# Rev_1.net
KiCad netlist of a schematic drawn in EAGLE
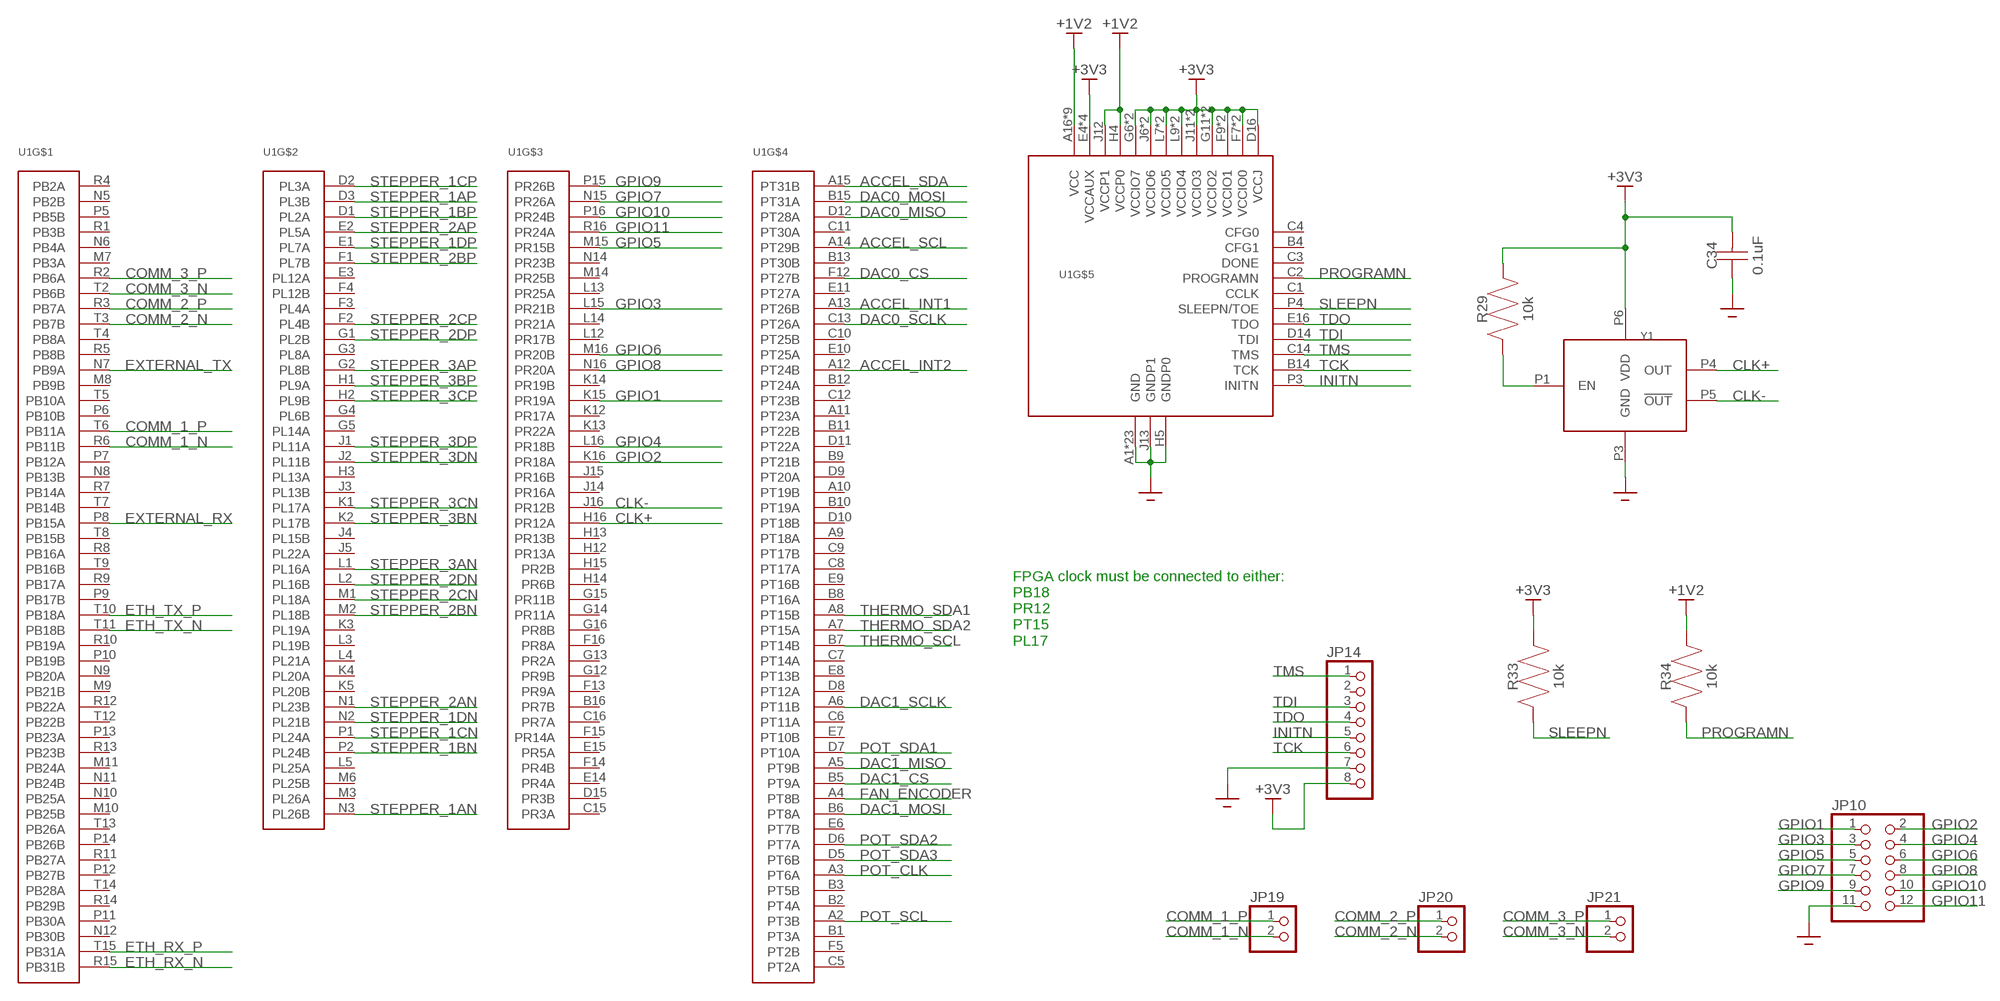
[diagram p0: schematic, sheet 1]
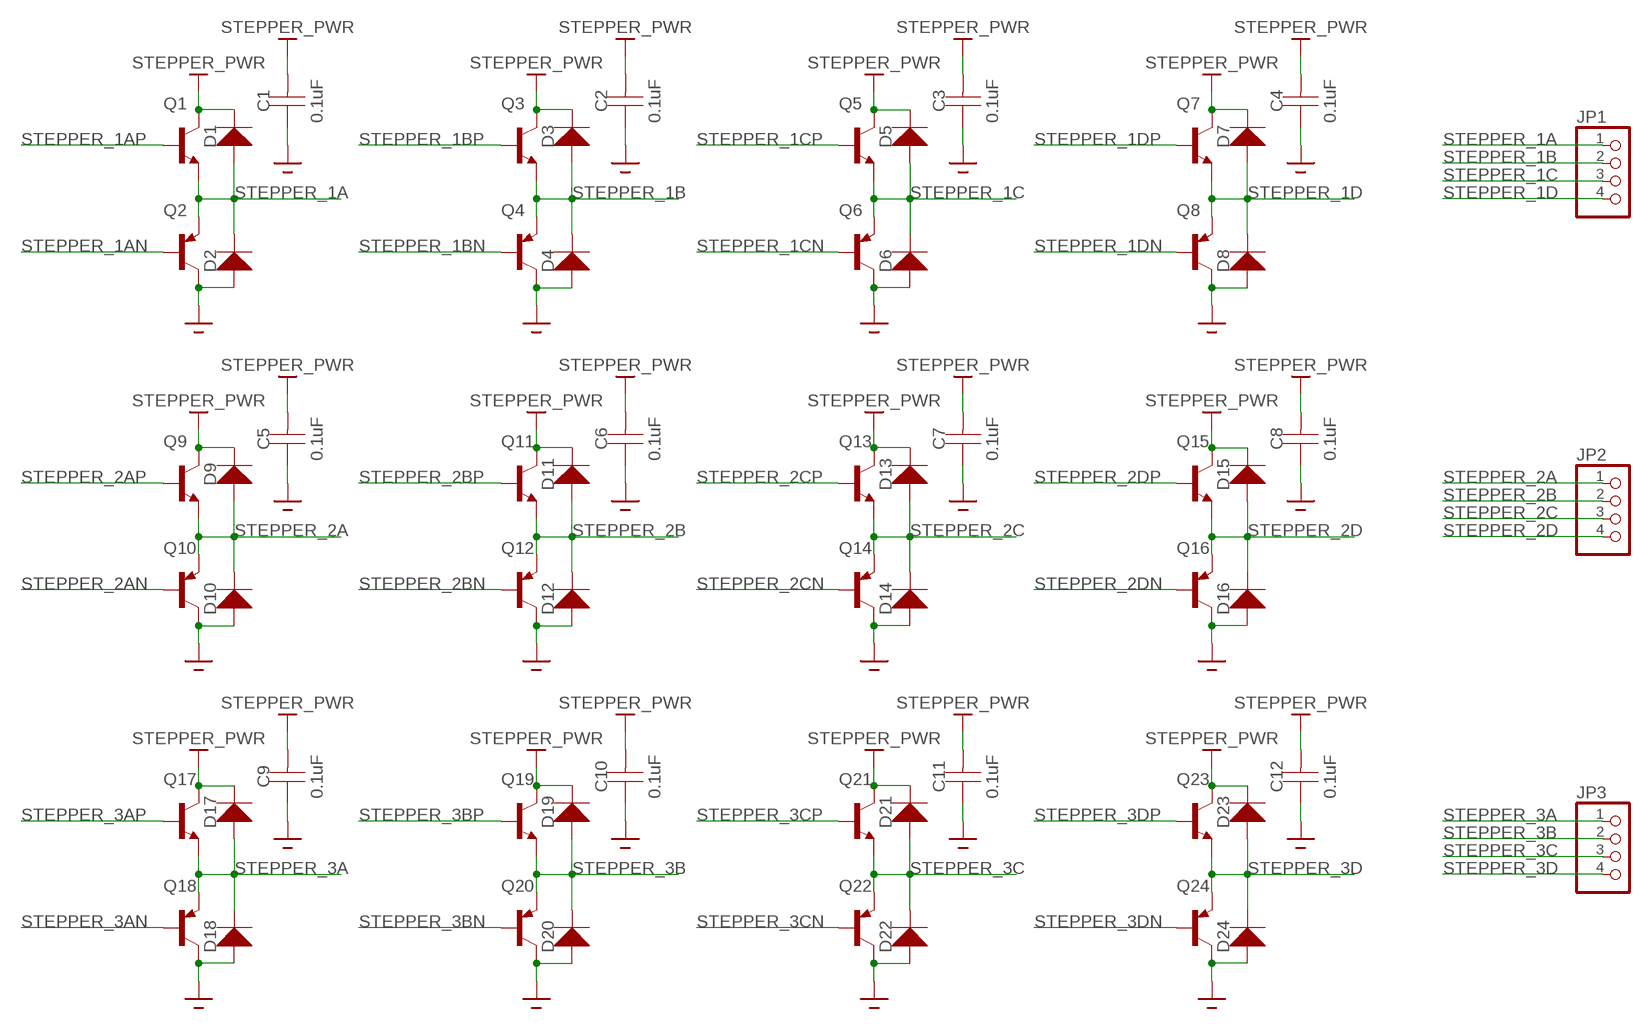
[diagram p1: schematic, sheet 2]
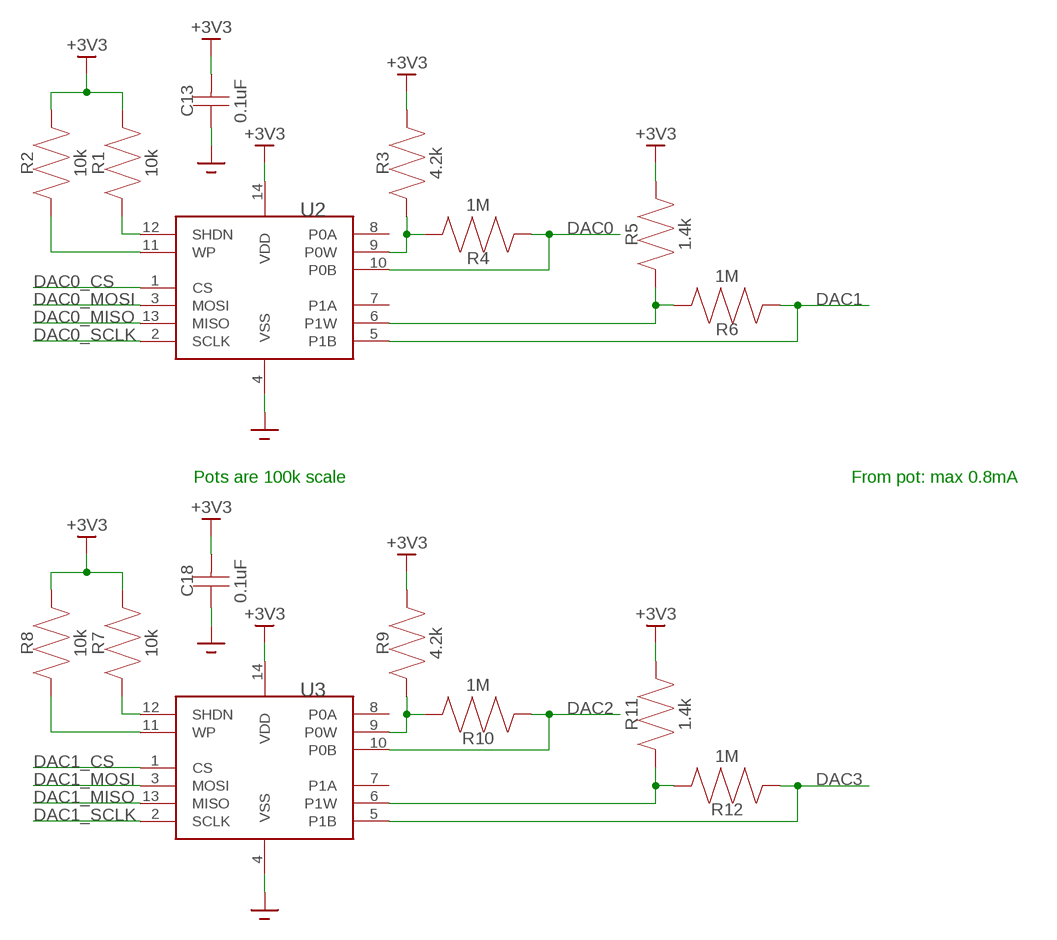
[diagram p2: schematic, sheet 3]
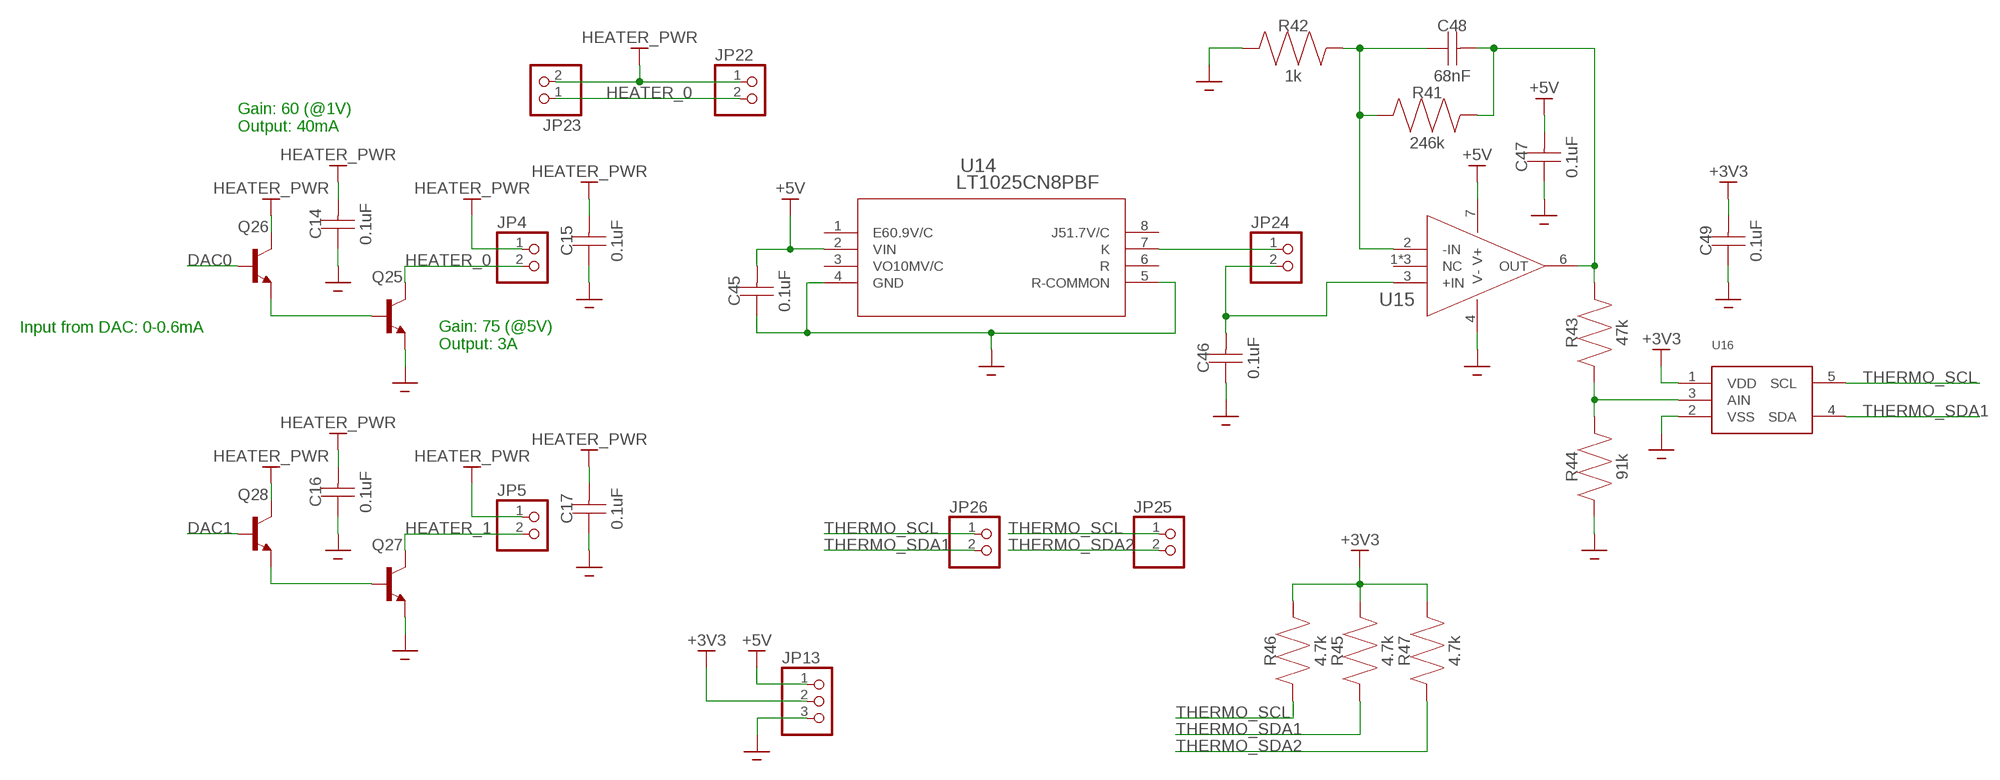
[diagram p3: schematic, sheet 4]
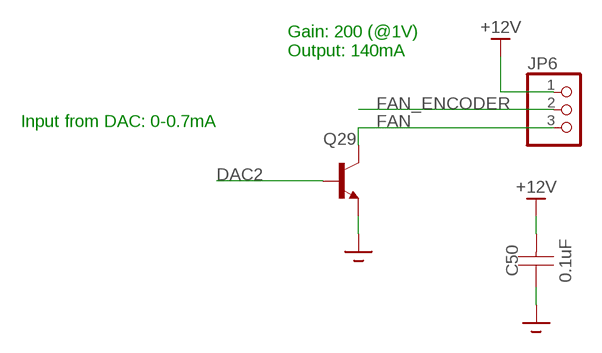
[diagram p4: schematic, sheet 5]
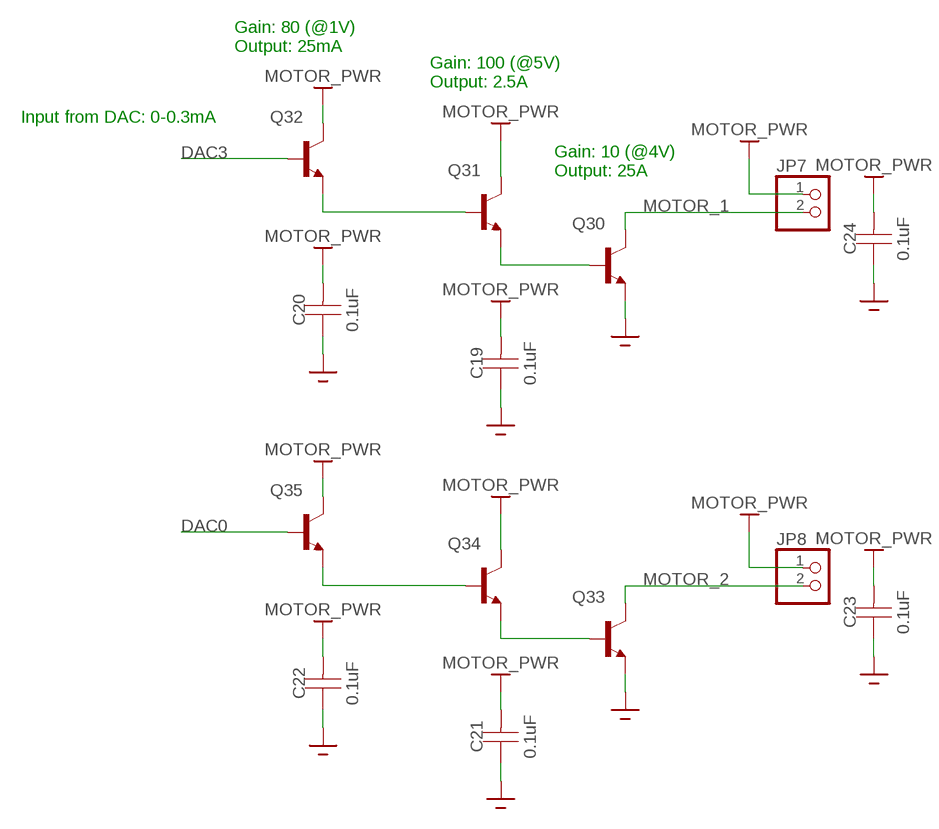
[diagram p5: schematic, sheet 6]
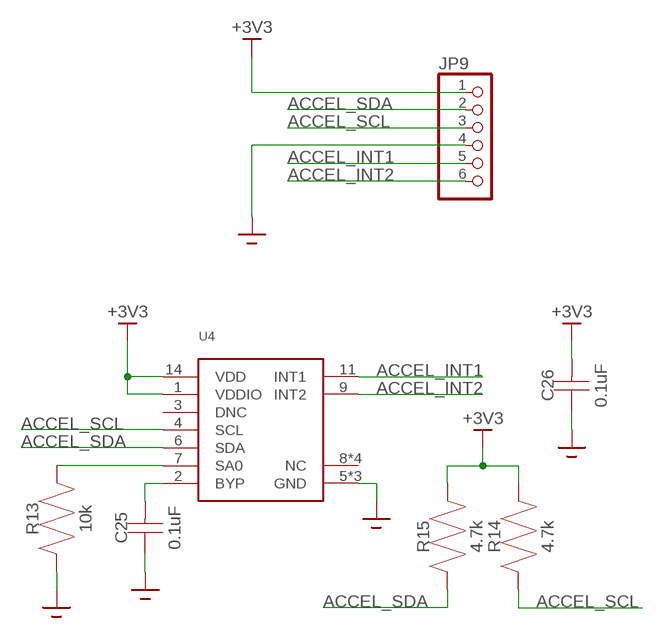
[diagram p6: schematic, sheet 7]
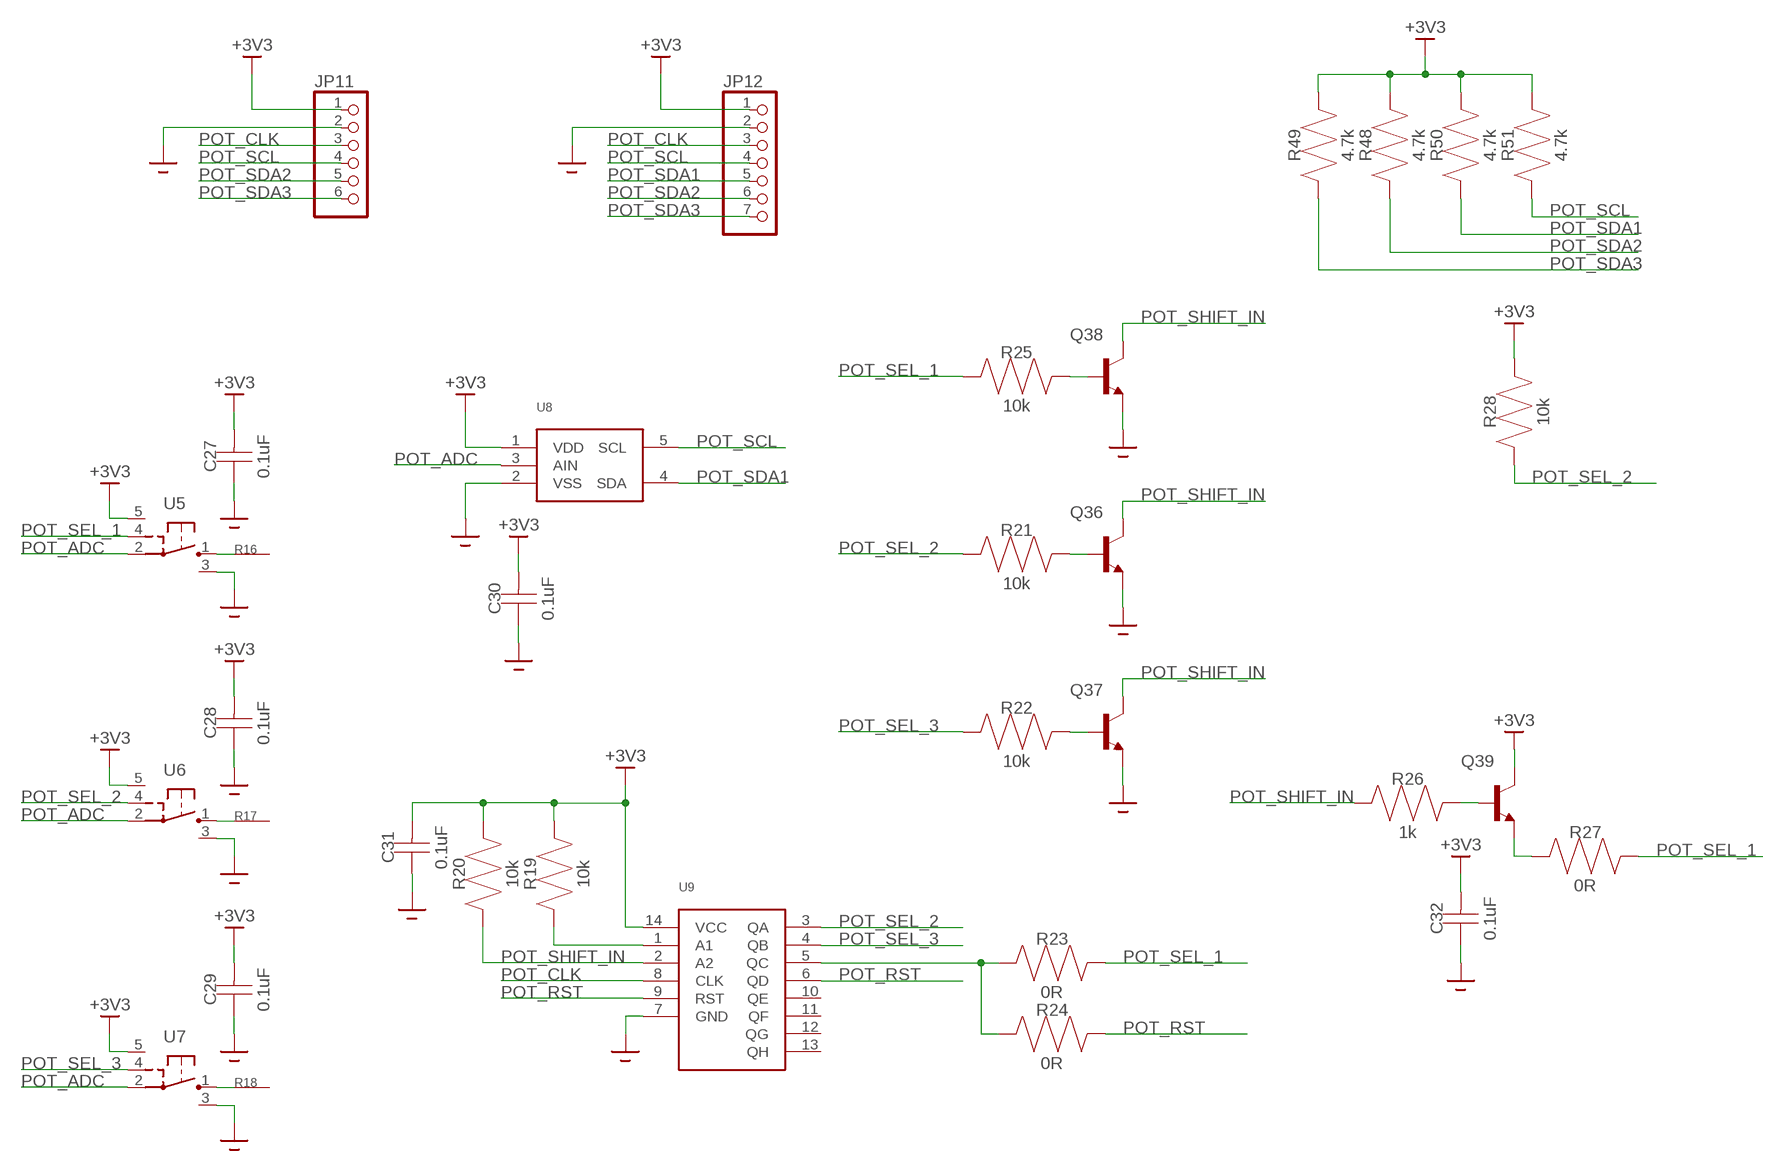
[diagram p7: schematic, sheet 8]
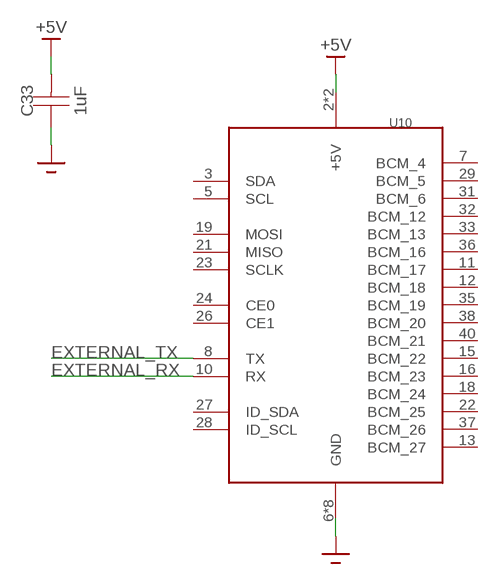
[diagram p8: schematic, sheet 9]
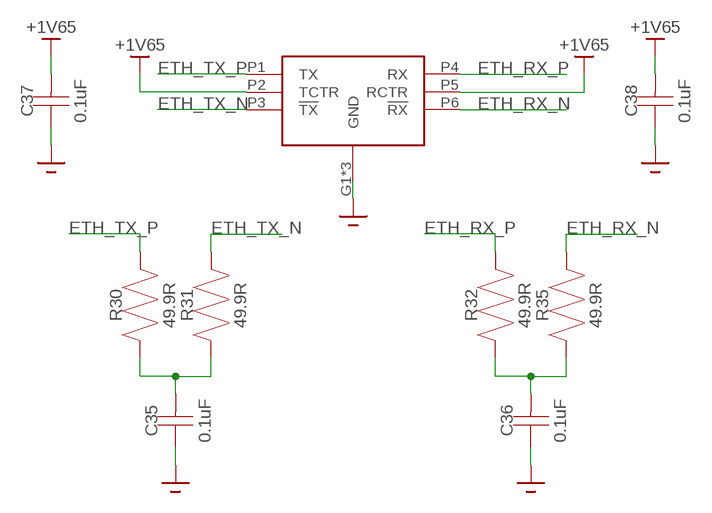
[diagram p9: schematic, sheet 10]
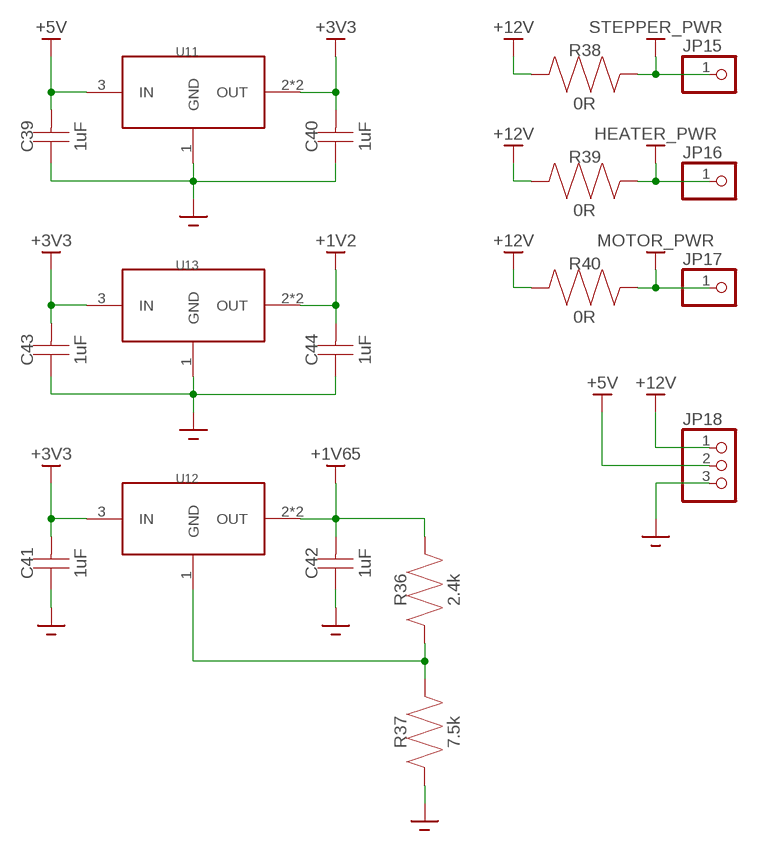
[diagram p10: schematic, sheet 11]
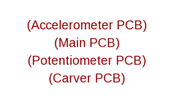
[diagram p11: schematic, sheet 12]

(export (version "E")
  (design (tool "Eeschema 10.0.6"))
  (components
    (comp (ref "C35")
      (value "0.1uF")
      (footprint "eagle-import:0805")
      (libsource (lib "eagle-import") (part "CAPACITOR0805"))
    )
    (comp (ref "C36")
      (value "0.1uF")
      (footprint "eagle-import:0805")
      (libsource (lib "eagle-import") (part "CAPACITOR0805"))
    )
    (comp (ref "C37")
      (value "0.1uF")
      (footprint "eagle-import:0805")
      (libsource (lib "eagle-import") (part "CAPACITOR0805"))
    )
    (comp (ref "C38")
      (value "0.1uF")
      (footprint "eagle-import:0805")
      (libsource (lib "eagle-import") (part "CAPACITOR0805"))
    )
    (comp (ref "P1")
      (value "5-2301994-4")
      (footprint "eagle-import:5-2301994-4")
      (libsource (lib "eagle-import") (part "5-2301994-4"))
    )
    (comp (ref "R30")
      (value "49.9R")
      (footprint "eagle-import:0805")
      (libsource (lib "eagle-import") (part "RESISTOR0805"))
    )
    (comp (ref "R31")
      (value "49.9R")
      (footprint "eagle-import:0805")
      (libsource (lib "eagle-import") (part "RESISTOR0805"))
    )
    (comp (ref "R32")
      (value "49.9R")
      (footprint "eagle-import:0805")
      (libsource (lib "eagle-import") (part "RESISTOR0805"))
    )
    (comp (ref "R35")
      (value "49.9R")
      (footprint "eagle-import:0805")
      (libsource (lib "eagle-import") (part "RESISTOR0805"))
    )
    (comp (ref "C19")
      (value "0.1uF")
      (footprint "eagle-import:0805")
      (libsource (lib "eagle-import") (part "CAPACITOR0805"))
    )
    (comp (ref "C20")
      (value "0.1uF")
      (footprint "eagle-import:0805")
      (libsource (lib "eagle-import") (part "CAPACITOR0805"))
    )
    (comp (ref "C21")
      (value "0.1uF")
      (footprint "eagle-import:0805")
      (libsource (lib "eagle-import") (part "CAPACITOR0805"))
    )
    (comp (ref "C22")
      (value "0.1uF")
      (footprint "eagle-import:0805")
      (libsource (lib "eagle-import") (part "CAPACITOR0805"))
    )
    (comp (ref "C23")
      (value "0.1uF")
      (footprint "eagle-import:0805")
      (libsource (lib "eagle-import") (part "CAPACITOR0805"))
    )
    (comp (ref "C24")
      (value "0.1uF")
      (footprint "eagle-import:0805")
      (libsource (lib "eagle-import") (part "CAPACITOR0805"))
    )
    (comp (ref "JP7")
      (value "PINHD-1X2")
      (footprint "eagle-import:1X02")
      (libsource (lib "eagle-import") (part "PINHD-1X2"))
    )
    (comp (ref "JP8")
      (value "PINHD-1X2")
      (footprint "eagle-import:1X02")
      (libsource (lib "eagle-import") (part "PINHD-1X2"))
    )
    (comp (ref "Q30")
      (value "TIP35CTIP35C")
      (footprint "eagle-import:HDRV3W140P545_1X3_1560X508X838B")
      (libsource (lib "eagle-import") (part "TIP35CTIP35C"))
    )
    (comp (ref "Q31")
      (value "PBSS4360XFPBSS4360XF")
      (footprint "eagle-import:SOT150P400X160-4")
      (libsource (lib "eagle-import") (part "PBSS4360XFPBSS4360XF"))
    )
    (comp (ref "Q32")
      (value "MMBT3904,215MMBT3904,215")
      (footprint "eagle-import:SOT95P230X110-3")
      (libsource (lib "eagle-import") (part "MMBT3904,215MMBT3904,215"))
    )
    (comp (ref "Q33")
      (value "TIP35CTIP35C")
      (footprint "eagle-import:HDRV3W140P545_1X3_1560X508X838B")
      (libsource (lib "eagle-import") (part "TIP35CTIP35C"))
    )
    (comp (ref "Q34")
      (value "PBSS4360XFPBSS4360XF")
      (footprint "eagle-import:SOT150P400X160-4")
      (libsource (lib "eagle-import") (part "PBSS4360XFPBSS4360XF"))
    )
    (comp (ref "Q35")
      (value "MMBT3904,215MMBT3904,215")
      (footprint "eagle-import:SOT95P230X110-3")
      (libsource (lib "eagle-import") (part "MMBT3904,215MMBT3904,215"))
    )
    (comp (ref "C13")
      (value "0.1uF")
      (footprint "eagle-import:0805")
      (libsource (lib "eagle-import") (part "CAPACITOR0805"))
    )
    (comp (ref "C18")
      (value "0.1uF")
      (footprint "eagle-import:0805")
      (libsource (lib "eagle-import") (part "CAPACITOR0805"))
    )
    (comp (ref "R1")
      (value "10k")
      (footprint "eagle-import:0805")
      (libsource (lib "eagle-import") (part "RESISTOR0805"))
    )
    (comp (ref "R2")
      (value "10k")
      (footprint "eagle-import:0805")
      (libsource (lib "eagle-import") (part "RESISTOR0805"))
    )
    (comp (ref "R3")
      (value "4.2k")
      (footprint "eagle-import:0805")
      (libsource (lib "eagle-import") (part "RESISTOR0805"))
    )
    (comp (ref "R4")
      (value "1M")
      (footprint "eagle-import:0805")
      (libsource (lib "eagle-import") (part "RESISTOR0805"))
    )
    (comp (ref "R5")
      (value "1.4k")
      (footprint "eagle-import:0805")
      (libsource (lib "eagle-import") (part "RESISTOR0805"))
    )
    (comp (ref "R6")
      (value "1M")
      (footprint "eagle-import:0805")
      (libsource (lib "eagle-import") (part "RESISTOR0805"))
    )
    (comp (ref "R7")
      (value "10k")
      (footprint "eagle-import:0805")
      (libsource (lib "eagle-import") (part "RESISTOR0805"))
    )
    (comp (ref "R8")
      (value "10k")
      (footprint "eagle-import:0805")
      (libsource (lib "eagle-import") (part "RESISTOR0805"))
    )
    (comp (ref "R9")
      (value "4.2k")
      (footprint "eagle-import:0805")
      (libsource (lib "eagle-import") (part "RESISTOR0805"))
    )
    (comp (ref "R10")
      (value "1M")
      (footprint "eagle-import:0805")
      (libsource (lib "eagle-import") (part "RESISTOR0805"))
    )
    (comp (ref "R11")
      (value "1.4k")
      (footprint "eagle-import:0805")
      (libsource (lib "eagle-import") (part "RESISTOR0805"))
    )
    (comp (ref "R12")
      (value "1M")
      (footprint "eagle-import:0805")
      (libsource (lib "eagle-import") (part "RESISTOR0805"))
    )
    (comp (ref "U2")
      (value "MCP4251")
      (footprint "eagle-import:SOP65P640X120-14")
      (libsource (lib "eagle-import") (part "MCP4251"))
    )
    (comp (ref "U3")
      (value "MCP4251")
      (footprint "eagle-import:SOP65P640X120-14")
      (libsource (lib "eagle-import") (part "MCP4251"))
    )
    (comp (ref "C39")
      (value "1uF")
      (footprint "eagle-import:0805")
      (libsource (lib "eagle-import") (part "CAPACITOR0805"))
    )
    (comp (ref "C40")
      (value "1uF")
      (footprint "eagle-import:0805")
      (libsource (lib "eagle-import") (part "CAPACITOR0805"))
    )
    (comp (ref "C41")
      (value "1uF")
      (footprint "eagle-import:0805")
      (libsource (lib "eagle-import") (part "CAPACITOR0805"))
    )
    (comp (ref "C42")
      (value "1uF")
      (footprint "eagle-import:0805")
      (libsource (lib "eagle-import") (part "CAPACITOR0805"))
    )
    (comp (ref "C43")
      (value "1uF")
      (footprint "eagle-import:0805")
      (libsource (lib "eagle-import") (part "CAPACITOR0805"))
    )
    (comp (ref "C44")
      (value "1uF")
      (footprint "eagle-import:0805")
      (libsource (lib "eagle-import") (part "CAPACITOR0805"))
    )
    (comp (ref "JP15")
      (value "PINHD-1X1")
      (footprint "eagle-import:1X01")
      (libsource (lib "eagle-import") (part "PINHD-1X1"))
    )
    (comp (ref "JP16")
      (value "PINHD-1X1")
      (footprint "eagle-import:1X01")
      (libsource (lib "eagle-import") (part "PINHD-1X1"))
    )
    (comp (ref "JP17")
      (value "PINHD-1X1")
      (footprint "eagle-import:1X01")
      (libsource (lib "eagle-import") (part "PINHD-1X1"))
    )
    (comp (ref "JP18")
      (value "PINHD-1X3")
      (footprint "eagle-import:1X03")
      (libsource (lib "eagle-import") (part "PINHD-1X3"))
    )
    (comp (ref "R36")
      (value "2.4k")
      (footprint "eagle-import:0805")
      (libsource (lib "eagle-import") (part "RESISTOR0805"))
    )
    (comp (ref "R37")
      (value "7.5k")
      (footprint "eagle-import:0805")
      (libsource (lib "eagle-import") (part "RESISTOR0805"))
    )
    (comp (ref "R38")
      (value "0R")
      (footprint "eagle-import:0805")
      (libsource (lib "eagle-import") (part "RESISTOR0805"))
    )
    (comp (ref "R39")
      (value "0R")
      (footprint "eagle-import:0805")
      (libsource (lib "eagle-import") (part "RESISTOR0805"))
    )
    (comp (ref "R40")
      (value "0R")
      (footprint "eagle-import:0805")
      (libsource (lib "eagle-import") (part "RESISTOR0805"))
    )
    (comp (ref "U11")
      (value "3.3V")
      (footprint "eagle-import:SOT230P700X180-4")
      (libsource (lib "eagle-import") (part "AZ1117E"))
    )
    (comp (ref "U12")
      (value "3.3V")
      (footprint "eagle-import:SOT230P700X180-4")
      (libsource (lib "eagle-import") (part "AZ1117E"))
    )
    (comp (ref "U13")
      (value "3.3V")
      (footprint "eagle-import:SOT230P700X180-4")
      (libsource (lib "eagle-import") (part "AZ1117E"))
    )
    (comp (ref "C1")
      (value "0.1uF")
      (footprint "eagle-import:0805")
      (libsource (lib "eagle-import") (part "CAPACITOR0805"))
    )
    (comp (ref "C2")
      (value "0.1uF")
      (footprint "eagle-import:0805")
      (libsource (lib "eagle-import") (part "CAPACITOR0805"))
    )
    (comp (ref "C3")
      (value "0.1uF")
      (footprint "eagle-import:0805")
      (libsource (lib "eagle-import") (part "CAPACITOR0805"))
    )
    (comp (ref "C4")
      (value "0.1uF")
      (footprint "eagle-import:0805")
      (libsource (lib "eagle-import") (part "CAPACITOR0805"))
    )
    (comp (ref "C5")
      (value "0.1uF")
      (footprint "eagle-import:0805")
      (libsource (lib "eagle-import") (part "CAPACITOR0805"))
    )
    (comp (ref "C6")
      (value "0.1uF")
      (footprint "eagle-import:0805")
      (libsource (lib "eagle-import") (part "CAPACITOR0805"))
    )
    (comp (ref "C7")
      (value "0.1uF")
      (footprint "eagle-import:0805")
      (libsource (lib "eagle-import") (part "CAPACITOR0805"))
    )
    (comp (ref "C8")
      (value "0.1uF")
      (footprint "eagle-import:0805")
      (libsource (lib "eagle-import") (part "CAPACITOR0805"))
    )
    (comp (ref "C9")
      (value "0.1uF")
      (footprint "eagle-import:0805")
      (libsource (lib "eagle-import") (part "CAPACITOR0805"))
    )
    (comp (ref "C10")
      (value "0.1uF")
      (footprint "eagle-import:0805")
      (libsource (lib "eagle-import") (part "CAPACITOR0805"))
    )
    (comp (ref "C11")
      (value "0.1uF")
      (footprint "eagle-import:0805")
      (libsource (lib "eagle-import") (part "CAPACITOR0805"))
    )
    (comp (ref "C12")
      (value "0.1uF")
      (footprint "eagle-import:0805")
      (libsource (lib "eagle-import") (part "CAPACITOR0805"))
    )
    (comp (ref "D1")
      (value "M7")
      (footprint "eagle-import:DIOC5327X220")
      (libsource (lib "eagle-import") (part "M7"))
    )
    (comp (ref "D2")
      (value "M7")
      (footprint "eagle-import:DIOC5327X220")
      (libsource (lib "eagle-import") (part "M7"))
    )
    (comp (ref "D3")
      (value "M7")
      (footprint "eagle-import:DIOC5327X220")
      (libsource (lib "eagle-import") (part "M7"))
    )
    (comp (ref "D4")
      (value "M7")
      (footprint "eagle-import:DIOC5327X220")
      (libsource (lib "eagle-import") (part "M7"))
    )
    (comp (ref "D5")
      (value "M7")
      (footprint "eagle-import:DIOC5327X220")
      (libsource (lib "eagle-import") (part "M7"))
    )
    (comp (ref "D6")
      (value "M7")
      (footprint "eagle-import:DIOC5327X220")
      (libsource (lib "eagle-import") (part "M7"))
    )
    (comp (ref "D7")
      (value "M7")
      (footprint "eagle-import:DIOC5327X220")
      (libsource (lib "eagle-import") (part "M7"))
    )
    (comp (ref "D8")
      (value "M7")
      (footprint "eagle-import:DIOC5327X220")
      (libsource (lib "eagle-import") (part "M7"))
    )
    (comp (ref "D9")
      (value "M7")
      (footprint "eagle-import:DIOC5327X220")
      (libsource (lib "eagle-import") (part "M7"))
    )
    (comp (ref "D10")
      (value "M7")
      (footprint "eagle-import:DIOC5327X220")
      (libsource (lib "eagle-import") (part "M7"))
    )
    (comp (ref "D11")
      (value "M7")
      (footprint "eagle-import:DIOC5327X220")
      (libsource (lib "eagle-import") (part "M7"))
    )
    (comp (ref "D12")
      (value "M7")
      (footprint "eagle-import:DIOC5327X220")
      (libsource (lib "eagle-import") (part "M7"))
    )
    (comp (ref "D13")
      (value "M7")
      (footprint "eagle-import:DIOC5327X220")
      (libsource (lib "eagle-import") (part "M7"))
    )
    (comp (ref "D14")
      (value "M7")
      (footprint "eagle-import:DIOC5327X220")
      (libsource (lib "eagle-import") (part "M7"))
    )
    (comp (ref "D15")
      (value "M7")
      (footprint "eagle-import:DIOC5327X220")
      (libsource (lib "eagle-import") (part "M7"))
    )
    (comp (ref "D16")
      (value "M7")
      (footprint "eagle-import:DIOC5327X220")
      (libsource (lib "eagle-import") (part "M7"))
    )
    (comp (ref "D17")
      (value "M7")
      (footprint "eagle-import:DIOC5327X220")
      (libsource (lib "eagle-import") (part "M7"))
    )
    (comp (ref "D18")
      (value "M7")
      (footprint "eagle-import:DIOC5327X220")
      (libsource (lib "eagle-import") (part "M7"))
    )
    (comp (ref "D19")
      (value "M7")
      (footprint "eagle-import:DIOC5327X220")
      (libsource (lib "eagle-import") (part "M7"))
    )
    (comp (ref "D20")
      (value "M7")
      (footprint "eagle-import:DIOC5327X220")
      (libsource (lib "eagle-import") (part "M7"))
    )
    (comp (ref "D21")
      (value "M7")
      (footprint "eagle-import:DIOC5327X220")
      (libsource (lib "eagle-import") (part "M7"))
    )
    (comp (ref "D22")
      (value "M7")
      (footprint "eagle-import:DIOC5327X220")
      (libsource (lib "eagle-import") (part "M7"))
    )
    (comp (ref "D23")
      (value "M7")
      (footprint "eagle-import:DIOC5327X220")
      (libsource (lib "eagle-import") (part "M7"))
    )
    (comp (ref "D24")
      (value "M7")
      (footprint "eagle-import:DIOC5327X220")
      (libsource (lib "eagle-import") (part "M7"))
    )
    (comp (ref "JP1")
      (value "PINHD-1X4")
      (footprint "eagle-import:1X04")
      (libsource (lib "eagle-import") (part "PINHD-1X4"))
    )
    (comp (ref "JP2")
      (value "PINHD-1X4")
      (footprint "eagle-import:1X04")
      (libsource (lib "eagle-import") (part "PINHD-1X4"))
    )
    (comp (ref "JP3")
      (value "PINHD-1X4")
      (footprint "eagle-import:1X04")
      (libsource (lib "eagle-import") (part "PINHD-1X4"))
    )
    (comp (ref "Q1")
      (value "BCV27")
      (footprint "eagle-import:SOT23-3")
      (libsource (lib "eagle-import") (part "BCV27"))
    )
    (comp (ref "Q2")
      (value "BCV26SOT23")
      (footprint "eagle-import:SOT23-3")
      (libsource (lib "eagle-import") (part "BCV26SOT23"))
    )
    (comp (ref "Q3")
      (value "BCV27")
      (footprint "eagle-import:SOT23-3")
      (libsource (lib "eagle-import") (part "BCV27"))
    )
    (comp (ref "Q4")
      (value "BCV26SOT23")
      (footprint "eagle-import:SOT23-3")
      (libsource (lib "eagle-import") (part "BCV26SOT23"))
    )
    (comp (ref "Q5")
      (value "BCV27")
      (footprint "eagle-import:SOT23-3")
      (libsource (lib "eagle-import") (part "BCV27"))
    )
    (comp (ref "Q6")
      (value "BCV26SOT23")
      (footprint "eagle-import:SOT23-3")
      (libsource (lib "eagle-import") (part "BCV26SOT23"))
    )
    (comp (ref "Q7")
      (value "BCV27")
      (footprint "eagle-import:SOT23-3")
      (libsource (lib "eagle-import") (part "BCV27"))
    )
    (comp (ref "Q8")
      (value "BCV26SOT23")
      (footprint "eagle-import:SOT23-3")
      (libsource (lib "eagle-import") (part "BCV26SOT23"))
    )
    (comp (ref "Q9")
      (value "BCV27")
      (footprint "eagle-import:SOT23-3")
      (libsource (lib "eagle-import") (part "BCV27"))
    )
    (comp (ref "Q10")
      (value "BCV26SOT23")
      (footprint "eagle-import:SOT23-3")
      (libsource (lib "eagle-import") (part "BCV26SOT23"))
    )
    (comp (ref "Q11")
      (value "BCV27")
      (footprint "eagle-import:SOT23-3")
      (libsource (lib "eagle-import") (part "BCV27"))
    )
    (comp (ref "Q12")
      (value "BCV26SOT23")
      (footprint "eagle-import:SOT23-3")
      (libsource (lib "eagle-import") (part "BCV26SOT23"))
    )
    (comp (ref "Q13")
      (value "BCV27")
      (footprint "eagle-import:SOT23-3")
      (libsource (lib "eagle-import") (part "BCV27"))
    )
    (comp (ref "Q14")
      (value "BCV26SOT23")
      (footprint "eagle-import:SOT23-3")
      (libsource (lib "eagle-import") (part "BCV26SOT23"))
    )
    (comp (ref "Q15")
      (value "BCV27")
      (footprint "eagle-import:SOT23-3")
      (libsource (lib "eagle-import") (part "BCV27"))
    )
    (comp (ref "Q16")
      (value "BCV26SOT23")
      (footprint "eagle-import:SOT23-3")
      (libsource (lib "eagle-import") (part "BCV26SOT23"))
    )
    (comp (ref "Q17")
      (value "BCV27")
      (footprint "eagle-import:SOT23-3")
      (libsource (lib "eagle-import") (part "BCV27"))
    )
    (comp (ref "Q18")
      (value "BCV26SOT23")
      (footprint "eagle-import:SOT23-3")
      (libsource (lib "eagle-import") (part "BCV26SOT23"))
    )
    (comp (ref "Q19")
      (value "BCV27")
      (footprint "eagle-import:SOT23-3")
      (libsource (lib "eagle-import") (part "BCV27"))
    )
    (comp (ref "Q20")
      (value "BCV26SOT23")
      (footprint "eagle-import:SOT23-3")
      (libsource (lib "eagle-import") (part "BCV26SOT23"))
    )
    (comp (ref "Q21")
      (value "BCV27")
      (footprint "eagle-import:SOT23-3")
      (libsource (lib "eagle-import") (part "BCV27"))
    )
    (comp (ref "Q22")
      (value "BCV26SOT23")
      (footprint "eagle-import:SOT23-3")
      (libsource (lib "eagle-import") (part "BCV26SOT23"))
    )
    (comp (ref "Q23")
      (value "BCV27")
      (footprint "eagle-import:SOT23-3")
      (libsource (lib "eagle-import") (part "BCV27"))
    )
    (comp (ref "Q24")
      (value "BCV26SOT23")
      (footprint "eagle-import:SOT23-3")
      (libsource (lib "eagle-import") (part "BCV26SOT23"))
    )
    (comp (ref "C25")
      (value "0.1uF")
      (footprint "eagle-import:0805")
      (libsource (lib "eagle-import") (part "CAPACITOR0805"))
    )
    (comp (ref "C26")
      (value "0.1uF")
      (footprint "eagle-import:0805")
      (libsource (lib "eagle-import") (part "CAPACITOR0805"))
    )
    (comp (ref "JP9")
      (value "PINHD-1X6")
      (footprint "eagle-import:1X06")
      (libsource (lib "eagle-import") (part "PINHD-1X6"))
    )
    (comp (ref "R13")
      (value "10k")
      (footprint "eagle-import:0805")
      (libsource (lib "eagle-import") (part "RESISTOR0805"))
    )
    (comp (ref "R14")
      (value "4.7k")
      (footprint "eagle-import:0805")
      (libsource (lib "eagle-import") (part "RESISTOR0805"))
    )
    (comp (ref "R15")
      (value "4.7k")
      (footprint "eagle-import:0805")
      (libsource (lib "eagle-import") (part "RESISTOR0805"))
    )
    (comp (ref "U4")
      (value "MMA8453QR116QFN")
      (footprint "eagle-import:16QFN")
      (libsource (lib "eagle-import") (part "MMA8453QR116QFN"))
    )
    (comp (ref "C33")
      (value "1uF")
      (footprint "eagle-import:0805")
      (libsource (lib "eagle-import") (part "CAPACITOR0805"))
    )
    (comp (ref "U10")
      (value "RPI")
      (footprint "eagle-import:RPI")
      (libsource (lib "eagle-import") (part "RPI"))
    )
    (comp (ref "C14")
      (value "0.1uF")
      (footprint "eagle-import:0805")
      (libsource (lib "eagle-import") (part "CAPACITOR0805"))
    )
    (comp (ref "C15")
      (value "0.1uF")
      (footprint "eagle-import:0805")
      (libsource (lib "eagle-import") (part "CAPACITOR0805"))
    )
    (comp (ref "C16")
      (value "0.1uF")
      (footprint "eagle-import:0805")
      (libsource (lib "eagle-import") (part "CAPACITOR0805"))
    )
    (comp (ref "C17")
      (value "0.1uF")
      (footprint "eagle-import:0805")
      (libsource (lib "eagle-import") (part "CAPACITOR0805"))
    )
    (comp (ref "C45")
      (value "0.1uF")
      (footprint "eagle-import:0805")
      (libsource (lib "eagle-import") (part "CAPACITOR0805"))
    )
    (comp (ref "C46")
      (value "0.1uF")
      (footprint "eagle-import:0805")
      (libsource (lib "eagle-import") (part "CAPACITOR0805"))
    )
    (comp (ref "C47")
      (value "0.1uF")
      (footprint "eagle-import:0805")
      (libsource (lib "eagle-import") (part "CAPACITOR0805"))
    )
    (comp (ref "C48")
      (value "68nF")
      (footprint "eagle-import:0805")
      (libsource (lib "eagle-import") (part "CAPACITOR0805"))
    )
    (comp (ref "C49")
      (value "0.1uF")
      (footprint "eagle-import:0805")
      (libsource (lib "eagle-import") (part "CAPACITOR0805"))
    )
    (comp (ref "JP4")
      (value "PINHD-1X2")
      (footprint "eagle-import:1X02")
      (libsource (lib "eagle-import") (part "PINHD-1X2"))
    )
    (comp (ref "JP5")
      (value "PINHD-1X2")
      (footprint "eagle-import:1X02")
      (libsource (lib "eagle-import") (part "PINHD-1X2"))
    )
    (comp (ref "JP13")
      (value "PINHD-1X3")
      (footprint "eagle-import:1X03")
      (libsource (lib "eagle-import") (part "PINHD-1X3"))
    )
    (comp (ref "JP22")
      (value "PINHD-1X2")
      (footprint "eagle-import:1X02")
      (libsource (lib "eagle-import") (part "PINHD-1X2"))
    )
    (comp (ref "JP23")
      (value "PINHD-1X2")
      (footprint "eagle-import:1X02")
      (libsource (lib "eagle-import") (part "PINHD-1X2"))
    )
    (comp (ref "JP24")
      (value "PINHD-1X2")
      (footprint "eagle-import:1X02")
      (libsource (lib "eagle-import") (part "PINHD-1X2"))
    )
    (comp (ref "JP25")
      (value "PINHD-1X2")
      (footprint "eagle-import:1X02")
      (libsource (lib "eagle-import") (part "PINHD-1X2"))
    )
    (comp (ref "JP26")
      (value "PINHD-1X2")
      (footprint "eagle-import:1X02")
      (libsource (lib "eagle-import") (part "PINHD-1X2"))
    )
    (comp (ref "Q25")
      (value "PBSS4360XFPBSS4360XF")
      (footprint "eagle-import:SOT150P400X160-4")
      (libsource (lib "eagle-import") (part "PBSS4360XFPBSS4360XF"))
    )
    (comp (ref "Q26")
      (value "MMBT3904,215MMBT3904,215")
      (footprint "eagle-import:SOT95P230X110-3")
      (libsource (lib "eagle-import") (part "MMBT3904,215MMBT3904,215"))
    )
    (comp (ref "Q27")
      (value "PBSS4360XFPBSS4360XF")
      (footprint "eagle-import:SOT150P400X160-4")
      (libsource (lib "eagle-import") (part "PBSS4360XFPBSS4360XF"))
    )
    (comp (ref "Q28")
      (value "MMBT3904,215MMBT3904,215")
      (footprint "eagle-import:SOT95P230X110-3")
      (libsource (lib "eagle-import") (part "MMBT3904,215MMBT3904,215"))
    )
    (comp (ref "R41")
      (value "246k")
      (footprint "eagle-import:0805")
      (libsource (lib "eagle-import") (part "RESISTOR0805"))
    )
    (comp (ref "R42")
      (value "1k")
      (footprint "eagle-import:0805")
      (libsource (lib "eagle-import") (part "RESISTOR0805"))
    )
    (comp (ref "R43")
      (value "47k")
      (footprint "eagle-import:0805")
      (libsource (lib "eagle-import") (part "RESISTOR0805"))
    )
    (comp (ref "R44")
      (value "91k")
      (footprint "eagle-import:0805")
      (libsource (lib "eagle-import") (part "RESISTOR0805"))
    )
    (comp (ref "R45")
      (value "4.7k")
      (footprint "eagle-import:0805")
      (libsource (lib "eagle-import") (part "RESISTOR0805"))
    )
    (comp (ref "R46")
      (value "4.7k")
      (footprint "eagle-import:0805")
      (libsource (lib "eagle-import") (part "RESISTOR0805"))
    )
    (comp (ref "R47")
      (value "4.7k")
      (footprint "eagle-import:0805")
      (libsource (lib "eagle-import") (part "RESISTOR0805"))
    )
    (comp (ref "U14")
      (value "LT1025CN8PBF")
      (footprint "eagle-import:N_8")
      (fields (field (name "MANUFACTURER_PART_NUMBER") "LT1025CN8#PBF"))
      (libsource (lib "eagle-import") (part "LT1025CN8PBF"))
    )
    (comp (ref "U15")
      (value "LTC1049CS8#PBF")
      (footprint "eagle-import:SO-8_S")
      (libsource (lib "eagle-import") (part "LTC1049CS8#PBF"))
    )
    (comp (ref "U16")
      (value "MCP3021A1T-E/OTSOT23")
      (footprint "eagle-import:SOT23-5")
      (libsource (lib "eagle-import") (part "MCP3021A1T-E/OTSOT23"))
    )
    (comp (ref "C50")
      (value "0.1uF")
      (footprint "eagle-import:0805")
      (libsource (lib "eagle-import") (part "CAPACITOR0805"))
    )
    (comp (ref "JP6")
      (value "PINHD-1X3")
      (footprint "eagle-import:1X03")
      (libsource (lib "eagle-import") (part "PINHD-1X3"))
    )
    (comp (ref "Q29")
      (value "PBSS4360XFPBSS4360XF")
      (footprint "eagle-import:SOT150P400X160-4")
      (libsource (lib "eagle-import") (part "PBSS4360XFPBSS4360XF"))
    )
    (comp (ref "U$1")
      (value "PCB_ACCEL")
      (footprint "eagle-import:PCB_ACCEL")
      (libsource (lib "eagle-import") (part "PCB_ACCEL"))
    )
    (comp (ref "U$2")
      (value "PCB_MAIN")
      (footprint "eagle-import:PCB_MAIN")
      (libsource (lib "eagle-import") (part "PCB_MAIN"))
    )
    (comp (ref "U$3")
      (value "PCB_POT")
      (footprint "eagle-import:PCB_POT")
      (libsource (lib "eagle-import") (part "PCB_POT"))
    )
    (comp (ref "U$4")
      (value "PCB_CARVER")
      (footprint "eagle-import:PCB_CARVER")
      (libsource (lib "eagle-import") (part "PCB_CARVER"))
    )
    (comp (ref "C27")
      (value "0.1uF")
      (footprint "eagle-import:0805")
      (libsource (lib "eagle-import") (part "CAPACITOR0805"))
    )
    (comp (ref "C28")
      (value "0.1uF")
      (footprint "eagle-import:0805")
      (libsource (lib "eagle-import") (part "CAPACITOR0805"))
    )
    (comp (ref "C29")
      (value "0.1uF")
      (footprint "eagle-import:0805")
      (libsource (lib "eagle-import") (part "CAPACITOR0805"))
    )
    (comp (ref "C30")
      (value "0.1uF")
      (footprint "eagle-import:0805")
      (libsource (lib "eagle-import") (part "CAPACITOR0805"))
    )
    (comp (ref "C31")
      (value "0.1uF")
      (footprint "eagle-import:0805")
      (libsource (lib "eagle-import") (part "CAPACITOR0805"))
    )
    (comp (ref "C32")
      (value "0.1uF")
      (footprint "eagle-import:0805")
      (libsource (lib "eagle-import") (part "CAPACITOR0805"))
    )
    (comp (ref "JP11")
      (value "PINHD-1X6")
      (footprint "eagle-import:1X06")
      (libsource (lib "eagle-import") (part "PINHD-1X6"))
    )
    (comp (ref "JP12")
      (value "PINHD-1X7")
      (footprint "eagle-import:1X07")
      (libsource (lib "eagle-import") (part "PINHD-1X7"))
    )
    (comp (ref "Q36")
      (value "MMBT3904,215MMBT3904,215")
      (footprint "eagle-import:SOT95P230X110-3")
      (libsource (lib "eagle-import") (part "MMBT3904,215MMBT3904,215"))
    )
    (comp (ref "Q37")
      (value "MMBT3904,215MMBT3904,215")
      (footprint "eagle-import:SOT95P230X110-3")
      (libsource (lib "eagle-import") (part "MMBT3904,215MMBT3904,215"))
    )
    (comp (ref "Q38")
      (value "MMBT3904,215MMBT3904,215")
      (footprint "eagle-import:SOT95P230X110-3")
      (libsource (lib "eagle-import") (part "MMBT3904,215MMBT3904,215"))
    )
    (comp (ref "Q39")
      (value "MMBT3904,215MMBT3904,215")
      (footprint "eagle-import:SOT95P230X110-3")
      (libsource (lib "eagle-import") (part "MMBT3904,215MMBT3904,215"))
    )
    (comp (ref "R16")
      (value "POTENTIOMETER")
      (footprint "eagle-import:POTENTIOMETER")
      (libsource (lib "eagle-import") (part "POTENTIOMETER"))
    )
    (comp (ref "R17")
      (value "POTENTIOMETER")
      (footprint "eagle-import:POTENTIOMETER")
      (libsource (lib "eagle-import") (part "POTENTIOMETER"))
    )
    (comp (ref "R18")
      (value "POTENTIOMETER")
      (footprint "eagle-import:POTENTIOMETER")
      (libsource (lib "eagle-import") (part "POTENTIOMETER"))
    )
    (comp (ref "R19")
      (value "10k")
      (footprint "eagle-import:0805")
      (libsource (lib "eagle-import") (part "RESISTOR0805"))
    )
    (comp (ref "R20")
      (value "10k")
      (footprint "eagle-import:0805")
      (libsource (lib "eagle-import") (part "RESISTOR0805"))
    )
    (comp (ref "R21")
      (value "10k")
      (footprint "eagle-import:0805")
      (libsource (lib "eagle-import") (part "RESISTOR0805"))
    )
    (comp (ref "R22")
      (value "10k")
      (footprint "eagle-import:0805")
      (libsource (lib "eagle-import") (part "RESISTOR0805"))
    )
    (comp (ref "R23")
      (value "0R")
      (footprint "eagle-import:0805")
      (libsource (lib "eagle-import") (part "RESISTOR0805"))
    )
    (comp (ref "R24")
      (value "0R")
      (footprint "eagle-import:0805")
      (libsource (lib "eagle-import") (part "RESISTOR0805"))
    )
    (comp (ref "R25")
      (value "10k")
      (footprint "eagle-import:0805")
      (libsource (lib "eagle-import") (part "RESISTOR0805"))
    )
    (comp (ref "R26")
      (value "1k")
      (footprint "eagle-import:0805")
      (libsource (lib "eagle-import") (part "RESISTOR0805"))
    )
    (comp (ref "R27")
      (value "0R")
      (footprint "eagle-import:0805")
      (libsource (lib "eagle-import") (part "RESISTOR0805"))
    )
    (comp (ref "R28")
      (value "10k")
      (footprint "eagle-import:0805")
      (libsource (lib "eagle-import") (part "RESISTOR0805"))
    )
    (comp (ref "R48")
      (value "4.7k")
      (footprint "eagle-import:0805")
      (libsource (lib "eagle-import") (part "RESISTOR0805"))
    )
    (comp (ref "R49")
      (value "4.7k")
      (footprint "eagle-import:0805")
      (libsource (lib "eagle-import") (part "RESISTOR0805"))
    )
    (comp (ref "R50")
      (value "4.7k")
      (footprint "eagle-import:0805")
      (libsource (lib "eagle-import") (part "RESISTOR0805"))
    )
    (comp (ref "R51")
      (value "4.7k")
      (footprint "eagle-import:0805")
      (libsource (lib "eagle-import") (part "RESISTOR0805"))
    )
    (comp (ref "U5")
      (value "74AHC1G66GW,125TSSOP6")
      (footprint "eagle-import:TSSOP5")
      (libsource (lib "eagle-import") (part "74AHC1G66GW,125TSSOP6"))
    )
    (comp (ref "U6")
      (value "74AHC1G66GW,125TSSOP6")
      (footprint "eagle-import:TSSOP5")
      (libsource (lib "eagle-import") (part "74AHC1G66GW,125TSSOP6"))
    )
    (comp (ref "U7")
      (value "74AHC1G66GW,125TSSOP6")
      (footprint "eagle-import:TSSOP5")
      (libsource (lib "eagle-import") (part "74AHC1G66GW,125TSSOP6"))
    )
    (comp (ref "U8")
      (value "MCP3021A1T-E/OTSOT23")
      (footprint "eagle-import:SOT23-5")
      (libsource (lib "eagle-import") (part "MCP3021A1T-E/OTSOT23"))
    )
    (comp (ref "U9")
      (value "MC74HC164BDR2GMC74HC164BDR2G")
      (footprint "eagle-import:SOIC127P600X175-14")
      (libsource (lib "eagle-import") (part "MC74HC164BDR2GMC74HC164BDR2G"))
    )
    (comp (ref "C34")
      (value "0.1uF")
      (footprint "eagle-import:0805")
      (libsource (lib "eagle-import") (part "CAPACITOR0805"))
    )
    (comp (ref "JP10")
      (value "PINHD-2X6")
      (footprint "eagle-import:2X06")
      (libsource (lib "eagle-import") (part "PINHD-2X6"))
    )
    (comp (ref "JP14")
      (value "PINHD-1X8")
      (footprint "eagle-import:1X08")
      (libsource (lib "eagle-import") (part "PINHD-1X8"))
    )
    (comp (ref "JP19")
      (value "PINHD-1X2")
      (footprint "eagle-import:1X02")
      (libsource (lib "eagle-import") (part "PINHD-1X2"))
    )
    (comp (ref "JP20")
      (value "PINHD-1X2")
      (footprint "eagle-import:1X02")
      (libsource (lib "eagle-import") (part "PINHD-1X2"))
    )
    (comp (ref "JP21")
      (value "PINHD-1X2")
      (footprint "eagle-import:1X02")
      (libsource (lib "eagle-import") (part "PINHD-1X2"))
    )
    (comp (ref "R29")
      (value "10k")
      (footprint "eagle-import:0805")
      (libsource (lib "eagle-import") (part "RESISTOR0805"))
    )
    (comp (ref "R33")
      (value "10k")
      (footprint "eagle-import:0805")
      (libsource (lib "eagle-import") (part "RESISTOR0805"))
    )
    (comp (ref "R34")
      (value "10k")
      (footprint "eagle-import:0805")
      (libsource (lib "eagle-import") (part "RESISTOR0805"))
    )
    (comp (ref "U1")
      (value "LFXP6E-3FN256C")
      (footprint "eagle-import:FBGA256")
      (libsource (lib "eagle-import") (part "LFXP6E-3FN256C"))
    )
    (comp (ref "Y1")
      (value "DSC1122B")
      (footprint "eagle-import:ICDFN500X320X90-4")
      (libsource (lib "eagle-import") (part "DSC1122B"))
    )
  )
  (nets
    (net (code "1") (name "+1V2") (class "Default")
      (node (ref "C44") (pin "P$2") (pinfunction "P$2_P$2") (pintype "passive"))
      (node (ref "R34") (pin "P$2") (pinfunction "P$2_P$2") (pintype "passive"))
      (node (ref "U1") (pin "A16") (pinfunction "VCC_A16") (pintype "bidirectional"))
      (node (ref "U1") (pin "D13") (pinfunction "VCC_D13") (pintype "bidirectional"))
      (node (ref "U1") (pin "D4") (pinfunction "VCC_D4") (pintype "bidirectional"))
      (node (ref "U1") (pin "E12") (pinfunction "VCC_E12") (pintype "bidirectional"))
      (node (ref "U1") (pin "E5") (pinfunction "VCC_E5") (pintype "bidirectional"))
      (node (ref "U1") (pin "H4") (pinfunction "VCCP0_H4") (pintype "bidirectional"))
      (node (ref "U1") (pin "J12") (pinfunction "VCCP1_J12") (pintype "bidirectional"))
      (node (ref "U1") (pin "M12") (pinfunction "VCC_M12") (pintype "bidirectional"))
      (node (ref "U1") (pin "M5") (pinfunction "VCC_M5") (pintype "bidirectional"))
      (node (ref "U1") (pin "N13") (pinfunction "VCC_N13") (pintype "bidirectional"))
      (node (ref "U1") (pin "N4") (pinfunction "VCC_N4") (pintype "bidirectional"))
      (node (ref "U13") (pin "2") (pinfunction "OUT_2") (pintype "power_in"))
      (node (ref "U13") (pin "4") (pinfunction "OUT_4") (pintype "power_in"))
    )
    (net (code "2") (name "+1V65") (class "Default")
      (node (ref "C37") (pin "P$2") (pinfunction "P$2_P$2") (pintype "passive"))
      (node (ref "C38") (pin "P$2") (pinfunction "P$2_P$2") (pintype "passive"))
      (node (ref "C42") (pin "P$2") (pinfunction "P$2_P$2") (pintype "passive"))
      (node (ref "P1") (pin "P2") (pinfunction "TCTR_P2") (pintype "input"))
      (node (ref "P1") (pin "P5") (pinfunction "RCTR_P5") (pintype "input"))
      (node (ref "R36") (pin "P$2") (pinfunction "P$2_P$2") (pintype "passive"))
      (node (ref "U12") (pin "2") (pinfunction "OUT_2") (pintype "power_in"))
      (node (ref "U12") (pin "4") (pinfunction "OUT_4") (pintype "power_in"))
    )
    (net (code "3") (name "+3V3") (class "Default")
      (node (ref "C13") (pin "P$2") (pinfunction "P$2_P$2") (pintype "passive"))
      (node (ref "C18") (pin "P$2") (pinfunction "P$2_P$2") (pintype "passive"))
      (node (ref "C26") (pin "P$2") (pinfunction "P$2_P$2") (pintype "passive"))
      (node (ref "C27") (pin "P$2") (pinfunction "P$2_P$2") (pintype "passive"))
      (node (ref "C28") (pin "P$2") (pinfunction "P$2_P$2") (pintype "passive"))
      (node (ref "C29") (pin "P$2") (pinfunction "P$2_P$2") (pintype "passive"))
      (node (ref "C30") (pin "P$2") (pinfunction "P$2_P$2") (pintype "passive"))
      (node (ref "C31") (pin "P$2") (pinfunction "P$2_P$2") (pintype "passive"))
      (node (ref "C32") (pin "P$2") (pinfunction "P$2_P$2") (pintype "passive"))
      (node (ref "C34") (pin "P$2") (pinfunction "P$2_P$2") (pintype "passive"))
      (node (ref "C40") (pin "P$2") (pinfunction "P$2_P$2") (pintype "passive"))
      (node (ref "C41") (pin "P$2") (pinfunction "P$2_P$2") (pintype "passive"))
      (node (ref "C43") (pin "P$2") (pinfunction "P$2_P$2") (pintype "passive"))
      (node (ref "C49") (pin "P$2") (pinfunction "P$2_P$2") (pintype "passive"))
      (node (ref "JP11") (pin "1") (pinfunction "1_1") (pintype "passive"))
      (node (ref "JP12") (pin "1") (pinfunction "1_1") (pintype "passive"))
      (node (ref "JP13") (pin "2") (pinfunction "2_2") (pintype "passive"))
      (node (ref "JP14") (pin "8") (pinfunction "8_8") (pintype "passive"))
      (node (ref "JP9") (pin "1") (pinfunction "1_1") (pintype "passive"))
      (node (ref "Q39") (pin "3") (pinfunction "C_3") (pintype "passive"))
      (node (ref "R1") (pin "P$2") (pinfunction "P$2_P$2") (pintype "passive"))
      (node (ref "R11") (pin "P$2") (pinfunction "P$2_P$2") (pintype "passive"))
      (node (ref "R14") (pin "P$2") (pinfunction "P$2_P$2") (pintype "passive"))
      (node (ref "R15") (pin "P$2") (pinfunction "P$2_P$2") (pintype "passive"))
      (node (ref "R19") (pin "P$2") (pinfunction "P$2_P$2") (pintype "passive"))
      (node (ref "R2") (pin "P$2") (pinfunction "P$2_P$2") (pintype "passive"))
      (node (ref "R20") (pin "P$2") (pinfunction "P$2_P$2") (pintype "passive"))
      (node (ref "R28") (pin "P$2") (pinfunction "P$2_P$2") (pintype "passive"))
      (node (ref "R29") (pin "P$2") (pinfunction "P$2_P$2") (pintype "passive"))
      (node (ref "R3") (pin "P$2") (pinfunction "P$2_P$2") (pintype "passive"))
      (node (ref "R33") (pin "P$2") (pinfunction "P$2_P$2") (pintype "passive"))
      (node (ref "R45") (pin "P$2") (pinfunction "P$2_P$2") (pintype "passive"))
      (node (ref "R46") (pin "P$2") (pinfunction "P$2_P$2") (pintype "passive"))
      (node (ref "R47") (pin "P$2") (pinfunction "P$2_P$2") (pintype "passive"))
      (node (ref "R48") (pin "P$2") (pinfunction "P$2_P$2") (pintype "passive"))
      (node (ref "R49") (pin "P$2") (pinfunction "P$2_P$2") (pintype "passive"))
      (node (ref "R5") (pin "P$2") (pinfunction "P$2_P$2") (pintype "passive"))
      (node (ref "R50") (pin "P$2") (pinfunction "P$2_P$2") (pintype "passive"))
      (node (ref "R51") (pin "P$2") (pinfunction "P$2_P$2") (pintype "passive"))
      (node (ref "R7") (pin "P$2") (pinfunction "P$2_P$2") (pintype "passive"))
      (node (ref "R8") (pin "P$2") (pinfunction "P$2_P$2") (pintype "passive"))
      (node (ref "R9") (pin "P$2") (pinfunction "P$2_P$2") (pintype "passive"))
      (node (ref "U1") (pin "D16") (pinfunction "VCCJ_D16") (pintype "bidirectional"))
      (node (ref "U1") (pin "E13") (pinfunction "VCCAUX_E13") (pintype "bidirectional"))
      (node (ref "U1") (pin "E4") (pinfunction "VCCAUX_E4") (pintype "bidirectional"))
      (node (ref "U1") (pin "F10") (pinfunction "VCCIO1_F10") (pintype "bidirectional"))
      (node (ref "U1") (pin "F7") (pinfunction "VCCIO0_F7") (pintype "bidirectional"))
      (node (ref "U1") (pin "F8") (pinfunction "VCCIO0_F8") (pintype "bidirectional"))
      (node (ref "U1") (pin "F9") (pinfunction "VCCIO1_F9") (pintype "bidirectional"))
      (node (ref "U1") (pin "G11") (pinfunction "VCCIO2_G11") (pintype "bidirectional"))
      (node (ref "U1") (pin "G6") (pinfunction "VCCIO7_G6") (pintype "bidirectional"))
      (node (ref "U1") (pin "H11") (pinfunction "VCCIO2_H11") (pintype "bidirectional"))
      (node (ref "U1") (pin "H6") (pinfunction "VCCIO7_H6") (pintype "bidirectional"))
      (node (ref "U1") (pin "J11") (pinfunction "VCCIO3_J11") (pintype "bidirectional"))
      (node (ref "U1") (pin "J6") (pinfunction "VCCIO6_J6") (pintype "bidirectional"))
      (node (ref "U1") (pin "K11") (pinfunction "VCCIO3_K11") (pintype "bidirectional"))
      (node (ref "U1") (pin "K6") (pinfunction "VCCIO6_K6") (pintype "bidirectional"))
      (node (ref "U1") (pin "L10") (pinfunction "VCCIO4_L10") (pintype "bidirectional"))
      (node (ref "U1") (pin "L7") (pinfunction "VCCIO5_L7") (pintype "bidirectional"))
      (node (ref "U1") (pin "L8") (pinfunction "VCCIO5_L8") (pintype "bidirectional"))
      (node (ref "U1") (pin "L9") (pinfunction "VCCIO4_L9") (pintype "bidirectional"))
      (node (ref "U1") (pin "M13") (pinfunction "VCCAUX_M13") (pintype "bidirectional"))
      (node (ref "U1") (pin "M4") (pinfunction "VCCAUX_M4") (pintype "bidirectional"))
      (node (ref "U11") (pin "2") (pinfunction "OUT_2") (pintype "power_in"))
      (node (ref "U11") (pin "4") (pinfunction "OUT_4") (pintype "power_in"))
      (node (ref "U12") (pin "3") (pinfunction "IN_3") (pintype "power_in"))
      (node (ref "U13") (pin "3") (pinfunction "IN_3") (pintype "power_in"))
      (node (ref "U16") (pin "1") (pinfunction "VDD_1") (pintype "bidirectional"))
      (node (ref "U2") (pin "14") (pinfunction "VDD_14") (pintype "power_in"))
      (node (ref "U3") (pin "14") (pinfunction "VDD_14") (pintype "power_in"))
      (node (ref "U4") (pin "1") (pinfunction "VDDIO_1") (pintype "bidirectional"))
      (node (ref "U4") (pin "14") (pinfunction "VDD_14") (pintype "bidirectional"))
      (node (ref "U5") (pin "5") (pinfunction "VCC_5") (pintype "passive"))
      (node (ref "U6") (pin "5") (pinfunction "VCC_5") (pintype "passive"))
      (node (ref "U7") (pin "5") (pinfunction "VCC_5") (pintype "passive"))
      (node (ref "U8") (pin "1") (pinfunction "VDD_1") (pintype "bidirectional"))
      (node (ref "U9") (pin "14") (pinfunction "VCC_14") (pintype "bidirectional"))
      (node (ref "Y1") (pin "P6") (pinfunction "VDD_P6") (pintype "power_in"))
    )
    (net (code "4") (name "+5V") (class "Default")
      (node (ref "C33") (pin "P$2") (pinfunction "P$2_P$2") (pintype "passive"))
      (node (ref "C39") (pin "P$2") (pinfunction "P$2_P$2") (pintype "passive"))
      (node (ref "C45") (pin "P$2") (pinfunction "P$2_P$2") (pintype "passive"))
      (node (ref "C47") (pin "P$2") (pinfunction "P$2_P$2") (pintype "passive"))
      (node (ref "JP13") (pin "1") (pinfunction "1_1") (pintype "passive"))
      (node (ref "JP18") (pin "2") (pinfunction "2_2") (pintype "passive"))
      (node (ref "U10") (pin "2") (pinfunction "+5V_2") (pintype "power_in"))
      (node (ref "U10") (pin "4") (pinfunction "+5V_4") (pintype "power_in"))
      (node (ref "U11") (pin "3") (pinfunction "IN_3") (pintype "power_in"))
      (node (ref "U14") (pin "2") (pinfunction "VIN_2") (pintype "passive"))
      (node (ref "U15") (pin "7") (pinfunction "V+_7") (pintype "power_in"))
    )
    (net (code "5") (name "+12V") (class "Default")
      (node (ref "C50") (pin "P$2") (pinfunction "P$2_P$2") (pintype "passive"))
      (node (ref "JP18") (pin "1") (pinfunction "1_1") (pintype "passive"))
      (node (ref "JP6") (pin "1") (pinfunction "1_1") (pintype "passive"))
      (node (ref "R38") (pin "P$1") (pinfunction "P$1_P$1") (pintype "passive"))
      (node (ref "R39") (pin "P$1") (pinfunction "P$1_P$1") (pintype "passive"))
      (node (ref "R40") (pin "P$1") (pinfunction "P$1_P$1") (pintype "passive"))
    )
    (net (code "6") (name "ACCEL_INT1") (class "Default")
      (node (ref "JP9") (pin "5") (pinfunction "5_5") (pintype "passive"))
      (node (ref "U1") (pin "A13") (pinfunction "PT26B_A13") (pintype "bidirectional"))
      (node (ref "U4") (pin "11") (pinfunction "INT1_11") (pintype "bidirectional"))
    )
    (net (code "7") (name "ACCEL_INT2") (class "Default")
      (node (ref "JP9") (pin "6") (pinfunction "6_6") (pintype "passive"))
      (node (ref "U1") (pin "A12") (pinfunction "PT24B_A12") (pintype "bidirectional"))
      (node (ref "U4") (pin "9") (pinfunction "INT2_9") (pintype "bidirectional"))
    )
    (net (code "8") (name "ACCEL_SCL") (class "Default")
      (node (ref "JP9") (pin "3") (pinfunction "3_3") (pintype "passive"))
      (node (ref "R14") (pin "P$1") (pinfunction "P$1_P$1") (pintype "passive"))
      (node (ref "U1") (pin "A14") (pinfunction "PT29B_A14") (pintype "bidirectional"))
      (node (ref "U4") (pin "4") (pinfunction "SCL_4") (pintype "bidirectional"))
    )
    (net (code "9") (name "ACCEL_SDA") (class "Default")
      (node (ref "JP9") (pin "2") (pinfunction "2_2") (pintype "passive"))
      (node (ref "R15") (pin "P$1") (pinfunction "P$1_P$1") (pintype "passive"))
      (node (ref "U1") (pin "A15") (pinfunction "PT31B_A15") (pintype "bidirectional"))
      (node (ref "U4") (pin "6") (pinfunction "SDA_6") (pintype "bidirectional"))
    )
    (net (code "10") (name "CLK+") (class "Default")
      (node (ref "U1") (pin "H16") (pinfunction "PR12A_H16") (pintype "bidirectional"))
      (node (ref "Y1") (pin "P4") (pinfunction "OUT_P4") (pintype "output"))
    )
    (net (code "11") (name "CLK-") (class "Default")
      (node (ref "U1") (pin "J16") (pinfunction "PR12B_J16") (pintype "bidirectional"))
      (node (ref "Y1") (pin "P5") (pinfunction "~{OUT}_P5") (pintype "output"))
    )
    (net (code "12") (name "COMM_1_N") (class "Default")
      (node (ref "JP19") (pin "2") (pinfunction "2_2") (pintype "passive"))
      (node (ref "U1") (pin "R6") (pinfunction "PB11B_R6") (pintype "bidirectional"))
    )
    (net (code "13") (name "COMM_1_P") (class "Default")
      (node (ref "JP19") (pin "1") (pinfunction "1_1") (pintype "passive"))
      (node (ref "U1") (pin "T6") (pinfunction "PB11A_T6") (pintype "bidirectional"))
    )
    (net (code "14") (name "COMM_2_N") (class "Default")
      (node (ref "JP20") (pin "2") (pinfunction "2_2") (pintype "passive"))
      (node (ref "U1") (pin "T3") (pinfunction "PB7B_T3") (pintype "bidirectional"))
    )
    (net (code "15") (name "COMM_2_P") (class "Default")
      (node (ref "JP20") (pin "1") (pinfunction "1_1") (pintype "passive"))
      (node (ref "U1") (pin "R3") (pinfunction "PB7A_R3") (pintype "bidirectional"))
    )
    (net (code "16") (name "COMM_3_N") (class "Default")
      (node (ref "JP21") (pin "2") (pinfunction "2_2") (pintype "passive"))
      (node (ref "U1") (pin "T2") (pinfunction "PB6B_T2") (pintype "bidirectional"))
    )
    (net (code "17") (name "COMM_3_P") (class "Default")
      (node (ref "JP21") (pin "1") (pinfunction "1_1") (pintype "passive"))
      (node (ref "U1") (pin "R2") (pinfunction "PB6A_R2") (pintype "bidirectional"))
    )
    (net (code "18") (name "DAC0") (class "Default")
      (node (ref "Q26") (pin "1") (pinfunction "B_1") (pintype "passive"))
      (node (ref "Q35") (pin "1") (pinfunction "B_1") (pintype "passive"))
      (node (ref "R4") (pin "P$1") (pinfunction "P$1_P$1") (pintype "passive"))
      (node (ref "U2") (pin "10") (pinfunction "P0B_10") (pintype "bidirectional"))
    )
    (net (code "19") (name "DAC0_CS") (class "Default")
      (node (ref "U1") (pin "F12") (pinfunction "PT27B_F12") (pintype "bidirectional"))
      (node (ref "U2") (pin "1") (pinfunction "CS_1") (pintype "bidirectional"))
    )
    (net (code "20") (name "DAC0_MISO") (class "Default")
      (node (ref "U1") (pin "D12") (pinfunction "PT28A_D12") (pintype "bidirectional"))
      (node (ref "U2") (pin "13") (pinfunction "MISO_13") (pintype "bidirectional"))
    )
    (net (code "21") (name "DAC0_MOSI") (class "Default")
      (node (ref "U1") (pin "B15") (pinfunction "PT31A_B15") (pintype "bidirectional"))
      (node (ref "U2") (pin "3") (pinfunction "MOSI_3") (pintype "bidirectional"))
    )
    (net (code "22") (name "DAC0_SCLK") (class "Default")
      (node (ref "U1") (pin "C13") (pinfunction "PT26A_C13") (pintype "bidirectional"))
      (node (ref "U2") (pin "2") (pinfunction "SCLK_2") (pintype "bidirectional"))
    )
    (net (code "23") (name "DAC1") (class "Default")
      (node (ref "Q28") (pin "1") (pinfunction "B_1") (pintype "passive"))
      (node (ref "R6") (pin "P$1") (pinfunction "P$1_P$1") (pintype "passive"))
      (node (ref "U2") (pin "5") (pinfunction "P1B_5") (pintype "bidirectional"))
    )
    (net (code "24") (name "DAC1_CS") (class "Default")
      (node (ref "U1") (pin "B5") (pinfunction "PT9A_B5") (pintype "bidirectional"))
      (node (ref "U3") (pin "1") (pinfunction "CS_1") (pintype "bidirectional"))
    )
    (net (code "25") (name "DAC1_MISO") (class "Default")
      (node (ref "U1") (pin "A5") (pinfunction "PT9B_A5") (pintype "bidirectional"))
      (node (ref "U3") (pin "13") (pinfunction "MISO_13") (pintype "bidirectional"))
    )
    (net (code "26") (name "DAC1_MOSI") (class "Default")
      (node (ref "U1") (pin "B6") (pinfunction "PT8A_B6") (pintype "bidirectional"))
      (node (ref "U3") (pin "3") (pinfunction "MOSI_3") (pintype "bidirectional"))
    )
    (net (code "27") (name "DAC1_SCLK") (class "Default")
      (node (ref "U1") (pin "A6") (pinfunction "PT11B_A6") (pintype "bidirectional"))
      (node (ref "U3") (pin "2") (pinfunction "SCLK_2") (pintype "bidirectional"))
    )
    (net (code "28") (name "DAC2") (class "Default")
      (node (ref "Q29") (pin "3") (pinfunction "B_3") (pintype "passive"))
      (node (ref "R10") (pin "P$1") (pinfunction "P$1_P$1") (pintype "passive"))
      (node (ref "U3") (pin "10") (pinfunction "P0B_10") (pintype "bidirectional"))
    )
    (net (code "29") (name "DAC3") (class "Default")
      (node (ref "Q32") (pin "1") (pinfunction "B_1") (pintype "passive"))
      (node (ref "R12") (pin "P$1") (pinfunction "P$1_P$1") (pintype "passive"))
      (node (ref "U3") (pin "5") (pinfunction "P1B_5") (pintype "bidirectional"))
    )
    (net (code "30") (name "ETH_RX_N") (class "Default")
      (node (ref "P1") (pin "P6") (pinfunction "~{RX}_P6") (pintype "bidirectional"))
      (node (ref "R35") (pin "P$2") (pinfunction "P$2_P$2") (pintype "passive"))
      (node (ref "U1") (pin "R15") (pinfunction "PB31B_R15") (pintype "bidirectional"))
    )
    (net (code "31") (name "ETH_RX_P") (class "Default")
      (node (ref "P1") (pin "P4") (pinfunction "RX_P4") (pintype "bidirectional"))
      (node (ref "R32") (pin "P$2") (pinfunction "P$2_P$2") (pintype "passive"))
      (node (ref "U1") (pin "T15") (pinfunction "PB31A_T15") (pintype "bidirectional"))
    )
    (net (code "32") (name "ETH_TX_N") (class "Default")
      (node (ref "P1") (pin "P3") (pinfunction "~{TX}_P3") (pintype "bidirectional"))
      (node (ref "R31") (pin "P$2") (pinfunction "P$2_P$2") (pintype "passive"))
      (node (ref "U1") (pin "T11") (pinfunction "PB18B_T11") (pintype "bidirectional"))
    )
    (net (code "33") (name "ETH_TX_P") (class "Default")
      (node (ref "P1") (pin "P1") (pinfunction "TX_P1") (pintype "bidirectional"))
      (node (ref "R30") (pin "P$2") (pinfunction "P$2_P$2") (pintype "passive"))
      (node (ref "U1") (pin "T10") (pinfunction "PB18A_T10") (pintype "bidirectional"))
    )
    (net (code "34") (name "EXTERNAL_RX") (class "Default")
      (node (ref "U1") (pin "P8") (pinfunction "PB15A_P8") (pintype "bidirectional"))
      (node (ref "U10") (pin "10") (pinfunction "RX_10") (pintype "bidirectional"))
    )
    (net (code "35") (name "EXTERNAL_TX") (class "Default")
      (node (ref "U1") (pin "N7") (pinfunction "PB9A_N7") (pintype "bidirectional"))
      (node (ref "U10") (pin "8") (pinfunction "TX_8") (pintype "bidirectional"))
    )
    (net (code "36") (name "FAN") (class "Default")
      (node (ref "JP6") (pin "3") (pinfunction "3_3") (pintype "passive"))
      (node (ref "Q29") (pin "2") (pinfunction "C_2") (pintype "passive"))
      (node (ref "Q29") (pin "4") (pinfunction "C_4") (pintype "passive"))
    )
    (net (code "37") (name "FAN_ENCODER") (class "Default")
      (node (ref "JP6") (pin "2") (pinfunction "2_2") (pintype "passive"))
      (node (ref "U1") (pin "A4") (pinfunction "PT8B_A4") (pintype "bidirectional"))
    )
    (net (code "38") (name "GND") (class "Default")
      (node (ref "C1") (pin "P$1") (pinfunction "P$1_P$1") (pintype "passive"))
      (node (ref "C10") (pin "P$1") (pinfunction "P$1_P$1") (pintype "passive"))
      (node (ref "C11") (pin "P$1") (pinfunction "P$1_P$1") (pintype "passive"))
      (node (ref "C12") (pin "P$1") (pinfunction "P$1_P$1") (pintype "passive"))
      (node (ref "C13") (pin "P$1") (pinfunction "P$1_P$1") (pintype "passive"))
      (node (ref "C14") (pin "P$1") (pinfunction "P$1_P$1") (pintype "passive"))
      (node (ref "C15") (pin "P$1") (pinfunction "P$1_P$1") (pintype "passive"))
      (node (ref "C16") (pin "P$1") (pinfunction "P$1_P$1") (pintype "passive"))
      (node (ref "C17") (pin "P$1") (pinfunction "P$1_P$1") (pintype "passive"))
      (node (ref "C18") (pin "P$1") (pinfunction "P$1_P$1") (pintype "passive"))
      (node (ref "C19") (pin "P$1") (pinfunction "P$1_P$1") (pintype "passive"))
      (node (ref "C2") (pin "P$1") (pinfunction "P$1_P$1") (pintype "passive"))
      (node (ref "C20") (pin "P$1") (pinfunction "P$1_P$1") (pintype "passive"))
      (node (ref "C21") (pin "P$1") (pinfunction "P$1_P$1") (pintype "passive"))
      (node (ref "C22") (pin "P$1") (pinfunction "P$1_P$1") (pintype "passive"))
      (node (ref "C23") (pin "P$1") (pinfunction "P$1_P$1") (pintype "passive"))
      (node (ref "C24") (pin "P$1") (pinfunction "P$1_P$1") (pintype "passive"))
      (node (ref "C25") (pin "P$1") (pinfunction "P$1_P$1") (pintype "passive"))
      (node (ref "C26") (pin "P$1") (pinfunction "P$1_P$1") (pintype "passive"))
      (node (ref "C27") (pin "P$1") (pinfunction "P$1_P$1") (pintype "passive"))
      (node (ref "C28") (pin "P$1") (pinfunction "P$1_P$1") (pintype "passive"))
      (node (ref "C29") (pin "P$1") (pinfunction "P$1_P$1") (pintype "passive"))
      (node (ref "C3") (pin "P$1") (pinfunction "P$1_P$1") (pintype "passive"))
      (node (ref "C30") (pin "P$1") (pinfunction "P$1_P$1") (pintype "passive"))
      (node (ref "C31") (pin "P$1") (pinfunction "P$1_P$1") (pintype "passive"))
      (node (ref "C32") (pin "P$1") (pinfunction "P$1_P$1") (pintype "passive"))
      (node (ref "C33") (pin "P$1") (pinfunction "P$1_P$1") (pintype "passive"))
      (node (ref "C34") (pin "P$1") (pinfunction "P$1_P$1") (pintype "passive"))
      (node (ref "C35") (pin "P$1") (pinfunction "P$1_P$1") (pintype "passive"))
      (node (ref "C36") (pin "P$1") (pinfunction "P$1_P$1") (pintype "passive"))
      (node (ref "C37") (pin "P$1") (pinfunction "P$1_P$1") (pintype "passive"))
      (node (ref "C38") (pin "P$1") (pinfunction "P$1_P$1") (pintype "passive"))
      (node (ref "C39") (pin "P$1") (pinfunction "P$1_P$1") (pintype "passive"))
      (node (ref "C4") (pin "P$1") (pinfunction "P$1_P$1") (pintype "passive"))
      (node (ref "C40") (pin "P$1") (pinfunction "P$1_P$1") (pintype "passive"))
      (node (ref "C41") (pin "P$1") (pinfunction "P$1_P$1") (pintype "passive"))
      (node (ref "C42") (pin "P$1") (pinfunction "P$1_P$1") (pintype "passive"))
      (node (ref "C43") (pin "P$1") (pinfunction "P$1_P$1") (pintype "passive"))
      (node (ref "C44") (pin "P$1") (pinfunction "P$1_P$1") (pintype "passive"))
      (node (ref "C45") (pin "P$1") (pinfunction "P$1_P$1") (pintype "passive"))
      (node (ref "C46") (pin "P$1") (pinfunction "P$1_P$1") (pintype "passive"))
      (node (ref "C47") (pin "P$1") (pinfunction "P$1_P$1") (pintype "passive"))
      (node (ref "C49") (pin "P$1") (pinfunction "P$1_P$1") (pintype "passive"))
      (node (ref "C5") (pin "P$1") (pinfunction "P$1_P$1") (pintype "passive"))
      (node (ref "C50") (pin "P$1") (pinfunction "P$1_P$1") (pintype "passive"))
      (node (ref "C6") (pin "P$1") (pinfunction "P$1_P$1") (pintype "passive"))
      (node (ref "C7") (pin "P$1") (pinfunction "P$1_P$1") (pintype "passive"))
      (node (ref "C8") (pin "P$1") (pinfunction "P$1_P$1") (pintype "passive"))
      (node (ref "C9") (pin "P$1") (pinfunction "P$1_P$1") (pintype "passive"))
      (node (ref "D10") (pin "1") (pinfunction "IN_1") (pintype "passive"))
      (node (ref "D12") (pin "1") (pinfunction "IN_1") (pintype "passive"))
      (node (ref "D14") (pin "1") (pinfunction "IN_1") (pintype "passive"))
      (node (ref "D16") (pin "1") (pinfunction "IN_1") (pintype "passive"))
      (node (ref "D18") (pin "1") (pinfunction "IN_1") (pintype "passive"))
      (node (ref "D2") (pin "1") (pinfunction "IN_1") (pintype "passive"))
      (node (ref "D20") (pin "1") (pinfunction "IN_1") (pintype "passive"))
      (node (ref "D22") (pin "1") (pinfunction "IN_1") (pintype "passive"))
      (node (ref "D24") (pin "1") (pinfunction "IN_1") (pintype "passive"))
      (node (ref "D4") (pin "1") (pinfunction "IN_1") (pintype "passive"))
      (node (ref "D6") (pin "1") (pinfunction "IN_1") (pintype "passive"))
      (node (ref "D8") (pin "1") (pinfunction "IN_1") (pintype "passive"))
      (node (ref "JP10") (pin "11") (pinfunction "11_11") (pintype "passive"))
      (node (ref "JP11") (pin "2") (pinfunction "2_2") (pintype "passive"))
      (node (ref "JP12") (pin "2") (pinfunction "2_2") (pintype "passive"))
      (node (ref "JP13") (pin "3") (pinfunction "3_3") (pintype "passive"))
      (node (ref "JP14") (pin "7") (pinfunction "7_7") (pintype "passive"))
      (node (ref "JP18") (pin "3") (pinfunction "3_3") (pintype "passive"))
      (node (ref "JP9") (pin "4") (pinfunction "4_4") (pintype "passive"))
      (node (ref "P1") (pin "G1") (pinfunction "GND_G1") (pintype "passive"))
      (node (ref "P1") (pin "G2") (pinfunction "GND_G2") (pintype "passive"))
      (node (ref "P1") (pin "P8") (pinfunction "GND_P8") (pintype "passive"))
      (node (ref "Q10") (pin "3") (pinfunction "C_3") (pintype "passive"))
      (node (ref "Q12") (pin "3") (pinfunction "C_3") (pintype "passive"))
      (node (ref "Q14") (pin "3") (pinfunction "C_3") (pintype "passive"))
      (node (ref "Q16") (pin "3") (pinfunction "C_3") (pintype "passive"))
      (node (ref "Q18") (pin "3") (pinfunction "C_3") (pintype "passive"))
      (node (ref "Q2") (pin "3") (pinfunction "C_3") (pintype "passive"))
      (node (ref "Q20") (pin "3") (pinfunction "C_3") (pintype "passive"))
      (node (ref "Q22") (pin "3") (pinfunction "C_3") (pintype "passive"))
      (node (ref "Q24") (pin "3") (pinfunction "C_3") (pintype "passive"))
      (node (ref "Q25") (pin "1") (pinfunction "E_1") (pintype "passive"))
      (node (ref "Q27") (pin "1") (pinfunction "E_1") (pintype "passive"))
      (node (ref "Q29") (pin "1") (pinfunction "E_1") (pintype "passive"))
      (node (ref "Q30") (pin "3") (pinfunction "E_3") (pintype "passive"))
      (node (ref "Q33") (pin "3") (pinfunction "E_3") (pintype "passive"))
      (node (ref "Q36") (pin "2") (pinfunction "E_2") (pintype "passive"))
      (node (ref "Q37") (pin "2") (pinfunction "E_2") (pintype "passive"))
      (node (ref "Q38") (pin "2") (pinfunction "E_2") (pintype "passive"))
      (node (ref "Q4") (pin "3") (pinfunction "C_3") (pintype "passive"))
      (node (ref "Q6") (pin "3") (pinfunction "C_3") (pintype "passive"))
      (node (ref "Q8") (pin "3") (pinfunction "C_3") (pintype "passive"))
      (node (ref "R13") (pin "P$1") (pinfunction "P$1_P$1") (pintype "passive"))
      (node (ref "R37") (pin "P$1") (pinfunction "P$1_P$1") (pintype "passive"))
      (node (ref "R42") (pin "P$1") (pinfunction "P$1_P$1") (pintype "passive"))
      (node (ref "R44") (pin "P$1") (pinfunction "P$1_P$1") (pintype "passive"))
      (node (ref "U1") (pin "A1") (pinfunction "GND_A1") (pintype "bidirectional"))
      (node (ref "U1") (pin "F11") (pinfunction "GND_F11") (pintype "bidirectional"))
      (node (ref "U1") (pin "F6") (pinfunction "GND_F6") (pintype "bidirectional"))
      (node (ref "U1") (pin "G10") (pinfunction "GND_G10") (pintype "bidirectional"))
      (node (ref "U1") (pin "G7") (pinfunction "GND_G7") (pintype "bidirectional"))
      (node (ref "U1") (pin "G8") (pinfunction "GND_G8") (pintype "bidirectional"))
      (node (ref "U1") (pin "G9") (pinfunction "GND_G9") (pintype "bidirectional"))
      (node (ref "U1") (pin "H10") (pinfunction "GND_H10") (pintype "bidirectional"))
      (node (ref "U1") (pin "H5") (pinfunction "GNDP0_H5") (pintype "bidirectional"))
      (node (ref "U1") (pin "H7") (pinfunction "GND_H7") (pintype "bidirectional"))
      (node (ref "U1") (pin "H8") (pinfunction "GND_H8") (pintype "bidirectional"))
      (node (ref "U1") (pin "H9") (pinfunction "GND_H9") (pintype "bidirectional"))
      (node (ref "U1") (pin "J10") (pinfunction "GND_J10") (pintype "bidirectional"))
      (node (ref "U1") (pin "J13") (pinfunction "GNDP1_J13") (pintype "bidirectional"))
      (node (ref "U1") (pin "J7") (pinfunction "GND_J7") (pintype "bidirectional"))
      (node (ref "U1") (pin "J8") (pinfunction "GND_J8") (pintype "bidirectional"))
      (node (ref "U1") (pin "J9") (pinfunction "GND_J9") (pintype "bidirectional"))
      (node (ref "U1") (pin "K10") (pinfunction "GND_K10") (pintype "bidirectional"))
      (node (ref "U1") (pin "K7") (pinfunction "GND_K7") (pintype "bidirectional"))
      (node (ref "U1") (pin "K8") (pinfunction "GND_K8") (pintype "bidirectional"))
      (node (ref "U1") (pin "K9") (pinfunction "GND_K9") (pintype "bidirectional"))
      (node (ref "U1") (pin "L11") (pinfunction "GND_L11") (pintype "bidirectional"))
      (node (ref "U1") (pin "L6") (pinfunction "GND_L6") (pintype "bidirectional"))
      (node (ref "U1") (pin "T1") (pinfunction "GND_T1") (pintype "bidirectional"))
      (node (ref "U1") (pin "T16") (pinfunction "GND_T16") (pintype "bidirectional"))
      (node (ref "U10") (pin "14") (pinfunction "GND_14") (pintype "passive"))
      (node (ref "U10") (pin "20") (pinfunction "GND_20") (pintype "passive"))
      (node (ref "U10") (pin "25") (pinfunction "GND_25") (pintype "passive"))
      (node (ref "U10") (pin "30") (pinfunction "GND_30") (pintype "passive"))
      (node (ref "U10") (pin "34") (pinfunction "GND_34") (pintype "passive"))
      (node (ref "U10") (pin "39") (pinfunction "GND_39") (pintype "passive"))
      (node (ref "U10") (pin "6") (pinfunction "GND_6") (pintype "passive"))
      (node (ref "U10") (pin "9") (pinfunction "GND_9") (pintype "passive"))
      (node (ref "U11") (pin "1") (pinfunction "GND_1") (pintype "passive"))
      (node (ref "U13") (pin "1") (pinfunction "GND_1") (pintype "passive"))
      (node (ref "U14") (pin "4") (pinfunction "GND_4") (pintype "passive"))
      (node (ref "U14") (pin "5") (pinfunction "R-COMMON_5") (pintype "passive"))
      (node (ref "U15") (pin "4") (pinfunction "V-_4") (pintype "power_in"))
      (node (ref "U16") (pin "2") (pinfunction "VSS_2") (pintype "bidirectional"))
      (node (ref "U2") (pin "4") (pinfunction "VSS_4") (pintype "passive"))
      (node (ref "U3") (pin "4") (pinfunction "VSS_4") (pintype "passive"))
      (node (ref "U4") (pin "10") (pinfunction "GND_10") (pintype "bidirectional"))
      (node (ref "U4") (pin "12") (pinfunction "GND_12") (pintype "bidirectional"))
      (node (ref "U4") (pin "5") (pinfunction "GND_5") (pintype "bidirectional"))
      (node (ref "U5") (pin "3") (pinfunction "GND_3") (pintype "passive"))
      (node (ref "U6") (pin "3") (pinfunction "GND_3") (pintype "passive"))
      (node (ref "U7") (pin "3") (pinfunction "GND_3") (pintype "passive"))
      (node (ref "U8") (pin "2") (pinfunction "VSS_2") (pintype "bidirectional"))
      (node (ref "U9") (pin "7") (pinfunction "GND_7") (pintype "bidirectional"))
      (node (ref "Y1") (pin "P3") (pinfunction "GND_P3") (pintype "passive"))
    )
    (net (code "39") (name "GPIO1") (class "Default")
      (node (ref "JP10") (pin "1") (pinfunction "1_1") (pintype "passive"))
      (node (ref "U1") (pin "K15") (pinfunction "PR19A_K15") (pintype "bidirectional"))
    )
    (net (code "40") (name "GPIO2") (class "Default")
      (node (ref "JP10") (pin "2") (pinfunction "2_2") (pintype "passive"))
      (node (ref "U1") (pin "K16") (pinfunction "PR18A_K16") (pintype "bidirectional"))
    )
    (net (code "41") (name "GPIO3") (class "Default")
      (node (ref "JP10") (pin "3") (pinfunction "3_3") (pintype "passive"))
      (node (ref "U1") (pin "L15") (pinfunction "PR21B_L15") (pintype "bidirectional"))
    )
    (net (code "42") (name "GPIO4") (class "Default")
      (node (ref "JP10") (pin "4") (pinfunction "4_4") (pintype "passive"))
      (node (ref "U1") (pin "L16") (pinfunction "PR18B_L16") (pintype "bidirectional"))
    )
    (net (code "43") (name "GPIO5") (class "Default")
      (node (ref "JP10") (pin "5") (pinfunction "5_5") (pintype "passive"))
      (node (ref "U1") (pin "M15") (pinfunction "PR15B_M15") (pintype "bidirectional"))
    )
    (net (code "44") (name "GPIO6") (class "Default")
      (node (ref "JP10") (pin "6") (pinfunction "6_6") (pintype "passive"))
      (node (ref "U1") (pin "M16") (pinfunction "PR20B_M16") (pintype "bidirectional"))
    )
    (net (code "45") (name "GPIO7") (class "Default")
      (node (ref "JP10") (pin "7") (pinfunction "7_7") (pintype "passive"))
      (node (ref "U1") (pin "N15") (pinfunction "PR26A_N15") (pintype "bidirectional"))
    )
    (net (code "46") (name "GPIO8") (class "Default")
      (node (ref "JP10") (pin "8") (pinfunction "8_8") (pintype "passive"))
      (node (ref "U1") (pin "N16") (pinfunction "PR20A_N16") (pintype "bidirectional"))
    )
    (net (code "47") (name "GPIO9") (class "Default")
      (node (ref "JP10") (pin "9") (pinfunction "9_9") (pintype "passive"))
      (node (ref "U1") (pin "P15") (pinfunction "PR26B_P15") (pintype "bidirectional"))
    )
    (net (code "48") (name "GPIO10") (class "Default")
      (node (ref "JP10") (pin "10") (pinfunction "10_10") (pintype "passive"))
      (node (ref "U1") (pin "P16") (pinfunction "PR24B_P16") (pintype "bidirectional"))
    )
    (net (code "49") (name "GPIO11") (class "Default")
      (node (ref "JP10") (pin "12") (pinfunction "12_12") (pintype "passive"))
      (node (ref "U1") (pin "R16") (pinfunction "PR24A_R16") (pintype "bidirectional"))
    )
    (net (code "50") (name "HEATER_0") (class "Default")
      (node (ref "JP22") (pin "2") (pinfunction "2_2") (pintype "passive"))
      (node (ref "JP23") (pin "1") (pinfunction "1_1") (pintype "passive"))
      (node (ref "JP4") (pin "2") (pinfunction "2_2") (pintype "passive"))
      (node (ref "Q25") (pin "2") (pinfunction "C_2") (pintype "passive"))
      (node (ref "Q25") (pin "4") (pinfunction "C_4") (pintype "passive"))
    )
    (net (code "51") (name "HEATER_1") (class "Default")
      (node (ref "JP5") (pin "2") (pinfunction "2_2") (pintype "passive"))
      (node (ref "Q27") (pin "2") (pinfunction "C_2") (pintype "passive"))
      (node (ref "Q27") (pin "4") (pinfunction "C_4") (pintype "passive"))
    )
    (net (code "52") (name "HEATER_PWR") (class "Default")
      (node (ref "C14") (pin "P$2") (pinfunction "P$2_P$2") (pintype "passive"))
      (node (ref "C15") (pin "P$2") (pinfunction "P$2_P$2") (pintype "passive"))
      (node (ref "C16") (pin "P$2") (pinfunction "P$2_P$2") (pintype "passive"))
      (node (ref "C17") (pin "P$2") (pinfunction "P$2_P$2") (pintype "passive"))
      (node (ref "JP16") (pin "1") (pinfunction "1_1") (pintype "passive"))
      (node (ref "JP22") (pin "1") (pinfunction "1_1") (pintype "passive"))
      (node (ref "JP23") (pin "2") (pinfunction "2_2") (pintype "passive"))
      (node (ref "JP4") (pin "1") (pinfunction "1_1") (pintype "passive"))
      (node (ref "JP5") (pin "1") (pinfunction "1_1") (pintype "passive"))
      (node (ref "Q26") (pin "3") (pinfunction "C_3") (pintype "passive"))
      (node (ref "Q28") (pin "3") (pinfunction "C_3") (pintype "passive"))
      (node (ref "R39") (pin "P$2") (pinfunction "P$2_P$2") (pintype "passive"))
    )
    (net (code "53") (name "INITN") (class "Default")
      (node (ref "JP14") (pin "5") (pinfunction "5_5") (pintype "passive"))
      (node (ref "U1") (pin "P3") (pinfunction "INITN_P3") (pintype "bidirectional"))
    )
    (net (code "54") (name "MOTOR_1") (class "Default")
      (node (ref "JP7") (pin "2") (pinfunction "2_2") (pintype "passive"))
      (node (ref "Q30") (pin "2") (pinfunction "C_2") (pintype "passive"))
    )
    (net (code "55") (name "MOTOR_2") (class "Default")
      (node (ref "JP8") (pin "2") (pinfunction "2_2") (pintype "passive"))
      (node (ref "Q33") (pin "2") (pinfunction "C_2") (pintype "passive"))
    )
    (net (code "56") (name "MOTOR_PWR") (class "Default")
      (node (ref "C19") (pin "P$2") (pinfunction "P$2_P$2") (pintype "passive"))
      (node (ref "C20") (pin "P$2") (pinfunction "P$2_P$2") (pintype "passive"))
      (node (ref "C21") (pin "P$2") (pinfunction "P$2_P$2") (pintype "passive"))
      (node (ref "C22") (pin "P$2") (pinfunction "P$2_P$2") (pintype "passive"))
      (node (ref "C23") (pin "P$2") (pinfunction "P$2_P$2") (pintype "passive"))
      (node (ref "C24") (pin "P$2") (pinfunction "P$2_P$2") (pintype "passive"))
      (node (ref "JP17") (pin "1") (pinfunction "1_1") (pintype "passive"))
      (node (ref "JP7") (pin "1") (pinfunction "1_1") (pintype "passive"))
      (node (ref "JP8") (pin "1") (pinfunction "1_1") (pintype "passive"))
      (node (ref "Q31") (pin "2") (pinfunction "C_2") (pintype "passive"))
      (node (ref "Q31") (pin "4") (pinfunction "C_4") (pintype "passive"))
      (node (ref "Q32") (pin "3") (pinfunction "C_3") (pintype "passive"))
      (node (ref "Q34") (pin "2") (pinfunction "C_2") (pintype "passive"))
      (node (ref "Q34") (pin "4") (pinfunction "C_4") (pintype "passive"))
      (node (ref "Q35") (pin "3") (pinfunction "C_3") (pintype "passive"))
      (node (ref "R40") (pin "P$2") (pinfunction "P$2_P$2") (pintype "passive"))
    )
    (net (code "57") (name "Net-(C35-PadP$2)") (class "Default")
      (node (ref "C35") (pin "P$2") (pinfunction "P$2_P$2") (pintype "passive"))
      (node (ref "R30") (pin "P$1") (pinfunction "P$1_P$1") (pintype "passive"))
      (node (ref "R31") (pin "P$1") (pinfunction "P$1_P$1") (pintype "passive"))
    )
    (net (code "58") (name "Net-(C36-PadP$2)") (class "Default")
      (node (ref "C36") (pin "P$2") (pinfunction "P$2_P$2") (pintype "passive"))
      (node (ref "R32") (pin "P$1") (pinfunction "P$1_P$1") (pintype "passive"))
      (node (ref "R35") (pin "P$1") (pinfunction "P$1_P$1") (pintype "passive"))
    )
    (net (code "59") (name "Net-(Q25-B)") (class "Default")
      (node (ref "Q25") (pin "3") (pinfunction "B_3") (pintype "passive"))
      (node (ref "Q26") (pin "2") (pinfunction "E_2") (pintype "passive"))
    )
    (net (code "60") (name "Net-(Q27-B)") (class "Default")
      (node (ref "Q27") (pin "3") (pinfunction "B_3") (pintype "passive"))
      (node (ref "Q28") (pin "2") (pinfunction "E_2") (pintype "passive"))
    )
    (net (code "61") (name "Net-(Q30-B)") (class "Default")
      (node (ref "Q30") (pin "1") (pinfunction "B_1") (pintype "passive"))
      (node (ref "Q31") (pin "1") (pinfunction "E_1") (pintype "passive"))
    )
    (net (code "62") (name "Net-(Q31-B)") (class "Default")
      (node (ref "Q31") (pin "3") (pinfunction "B_3") (pintype "passive"))
      (node (ref "Q32") (pin "2") (pinfunction "E_2") (pintype "passive"))
    )
    (net (code "63") (name "Net-(Q33-B)") (class "Default")
      (node (ref "Q33") (pin "1") (pinfunction "B_1") (pintype "passive"))
      (node (ref "Q34") (pin "1") (pinfunction "E_1") (pintype "passive"))
    )
    (net (code "64") (name "Net-(Q34-B)") (class "Default")
      (node (ref "Q34") (pin "3") (pinfunction "B_3") (pintype "passive"))
      (node (ref "Q35") (pin "2") (pinfunction "E_2") (pintype "passive"))
    )
    (net (code "65") (name "Net-(Q36-B)") (class "Default")
      (node (ref "Q36") (pin "1") (pinfunction "B_1") (pintype "passive"))
      (node (ref "R21") (pin "P$2") (pinfunction "P$2_P$2") (pintype "passive"))
    )
    (net (code "66") (name "Net-(Q37-B)") (class "Default")
      (node (ref "Q37") (pin "1") (pinfunction "B_1") (pintype "passive"))
      (node (ref "R22") (pin "P$2") (pinfunction "P$2_P$2") (pintype "passive"))
    )
    (net (code "67") (name "Net-(Q38-B)") (class "Default")
      (node (ref "Q38") (pin "1") (pinfunction "B_1") (pintype "passive"))
      (node (ref "R25") (pin "P$2") (pinfunction "P$2_P$2") (pintype "passive"))
    )
    (net (code "68") (name "Net-(Q39-B)") (class "Default")
      (node (ref "Q39") (pin "1") (pinfunction "B_1") (pintype "passive"))
      (node (ref "R26") (pin "P$2") (pinfunction "P$2_P$2") (pintype "passive"))
    )
    (net (code "69") (name "Net-(Q39-E)") (class "Default")
      (node (ref "Q39") (pin "2") (pinfunction "E_2") (pintype "passive"))
      (node (ref "R27") (pin "P$1") (pinfunction "P$1_P$1") (pintype "passive"))
    )
    (net (code "70") (name "Net-(U2-P0W)") (class "Default")
      (node (ref "R3") (pin "P$1") (pinfunction "P$1_P$1") (pintype "passive"))
      (node (ref "R4") (pin "P$2") (pinfunction "P$2_P$2") (pintype "passive"))
      (node (ref "U2") (pin "9") (pinfunction "P0W_9") (pintype "bidirectional"))
    )
    (net (code "71") (name "Net-(U2-P1W)") (class "Default")
      (node (ref "R5") (pin "P$1") (pinfunction "P$1_P$1") (pintype "passive"))
      (node (ref "R6") (pin "P$2") (pinfunction "P$2_P$2") (pintype "passive"))
      (node (ref "U2") (pin "6") (pinfunction "P1W_6") (pintype "bidirectional"))
    )
    (net (code "72") (name "Net-(U2-SHDN)") (class "Default")
      (node (ref "R1") (pin "P$1") (pinfunction "P$1_P$1") (pintype "passive"))
      (node (ref "U2") (pin "12") (pinfunction "SHDN_12") (pintype "bidirectional"))
    )
    (net (code "73") (name "Net-(U2-WP)") (class "Default")
      (node (ref "R2") (pin "P$1") (pinfunction "P$1_P$1") (pintype "passive"))
      (node (ref "U2") (pin "11") (pinfunction "WP_11") (pintype "bidirectional"))
    )
    (net (code "74") (name "Net-(U3-P0W)") (class "Default")
      (node (ref "R10") (pin "P$2") (pinfunction "P$2_P$2") (pintype "passive"))
      (node (ref "R9") (pin "P$1") (pinfunction "P$1_P$1") (pintype "passive"))
      (node (ref "U3") (pin "9") (pinfunction "P0W_9") (pintype "bidirectional"))
    )
    (net (code "75") (name "Net-(U3-P1W)") (class "Default")
      (node (ref "R11") (pin "P$1") (pinfunction "P$1_P$1") (pintype "passive"))
      (node (ref "R12") (pin "P$2") (pinfunction "P$2_P$2") (pintype "passive"))
      (node (ref "U3") (pin "6") (pinfunction "P1W_6") (pintype "bidirectional"))
    )
    (net (code "76") (name "Net-(U3-SHDN)") (class "Default")
      (node (ref "R7") (pin "P$1") (pinfunction "P$1_P$1") (pintype "passive"))
      (node (ref "U3") (pin "12") (pinfunction "SHDN_12") (pintype "bidirectional"))
    )
    (net (code "77") (name "Net-(U3-WP)") (class "Default")
      (node (ref "R8") (pin "P$1") (pinfunction "P$1_P$1") (pintype "passive"))
      (node (ref "U3") (pin "11") (pinfunction "WP_11") (pintype "bidirectional"))
    )
    (net (code "78") (name "Net-(U4-BYP)") (class "Default")
      (node (ref "C25") (pin "P$2") (pinfunction "P$2_P$2") (pintype "passive"))
      (node (ref "U4") (pin "2") (pinfunction "BYP_2") (pintype "bidirectional"))
    )
    (net (code "79") (name "Net-(U4-SA0)") (class "Default")
      (node (ref "R13") (pin "P$2") (pinfunction "P$2_P$2") (pintype "passive"))
      (node (ref "U4") (pin "7") (pinfunction "SA0_7") (pintype "bidirectional"))
    )
    (net (code "80") (name "Net-(U5-Y)") (class "Default")
      (node (ref "R16") (pin "P$1") (pinfunction "P$1_P$1") (pintype "input"))
      (node (ref "U5") (pin "1") (pinfunction "Y_1") (pintype "passive"))
    )
    (net (code "81") (name "Net-(U6-Y)") (class "Default")
      (node (ref "R17") (pin "P$1") (pinfunction "P$1_P$1") (pintype "input"))
      (node (ref "U6") (pin "1") (pinfunction "Y_1") (pintype "passive"))
    )
    (net (code "82") (name "Net-(U7-Y)") (class "Default")
      (node (ref "R18") (pin "P$1") (pinfunction "P$1_P$1") (pintype "input"))
      (node (ref "U7") (pin "1") (pinfunction "Y_1") (pintype "passive"))
    )
    (net (code "83") (name "Net-(U9-A1)") (class "Default")
      (node (ref "R19") (pin "P$1") (pinfunction "P$1_P$1") (pintype "passive"))
      (node (ref "U9") (pin "1") (pinfunction "A1_1") (pintype "bidirectional"))
    )
    (net (code "84") (name "Net-(U9-QC)") (class "Default")
      (node (ref "R23") (pin "P$1") (pinfunction "P$1_P$1") (pintype "passive"))
      (node (ref "R24") (pin "P$1") (pinfunction "P$1_P$1") (pintype "passive"))
      (node (ref "U9") (pin "5") (pinfunction "QC_5") (pintype "bidirectional"))
    )
    (net (code "85") (name "Net-(U12-GND)") (class "Default")
      (node (ref "R36") (pin "P$1") (pinfunction "P$1_P$1") (pintype "passive"))
      (node (ref "R37") (pin "P$2") (pinfunction "P$2_P$2") (pintype "passive"))
      (node (ref "U12") (pin "1") (pinfunction "GND_1") (pintype "passive"))
    )
    (net (code "86") (name "Net-(U14-K)") (class "Default")
      (node (ref "JP24") (pin "1") (pinfunction "1_1") (pintype "passive"))
      (node (ref "U14") (pin "7") (pinfunction "K_7") (pintype "passive"))
    )
    (net (code "87") (name "Net-(U15-+IN)") (class "Default")
      (node (ref "C46") (pin "P$2") (pinfunction "P$2_P$2") (pintype "passive"))
      (node (ref "JP24") (pin "2") (pinfunction "2_2") (pintype "passive"))
      (node (ref "U15") (pin "3") (pinfunction "+IN_3") (pintype "input"))
    )
    (net (code "88") (name "Net-(U15--IN)") (class "Default")
      (node (ref "C48") (pin "P$1") (pinfunction "P$1_P$1") (pintype "passive"))
      (node (ref "R41") (pin "P$1") (pinfunction "P$1_P$1") (pintype "passive"))
      (node (ref "R42") (pin "P$2") (pinfunction "P$2_P$2") (pintype "passive"))
      (node (ref "U15") (pin "2") (pinfunction "-IN_2") (pintype "input"))
    )
    (net (code "89") (name "Net-(U15-OUT)") (class "Default")
      (node (ref "C48") (pin "P$2") (pinfunction "P$2_P$2") (pintype "passive"))
      (node (ref "R41") (pin "P$2") (pinfunction "P$2_P$2") (pintype "passive"))
      (node (ref "R43") (pin "P$2") (pinfunction "P$2_P$2") (pintype "passive"))
      (node (ref "U15") (pin "6") (pinfunction "OUT_6") (pintype "output"))
    )
    (net (code "90") (name "Net-(U16-AIN)") (class "Default")
      (node (ref "R43") (pin "P$1") (pinfunction "P$1_P$1") (pintype "passive"))
      (node (ref "R44") (pin "P$2") (pinfunction "P$2_P$2") (pintype "passive"))
      (node (ref "U16") (pin "3") (pinfunction "AIN_3") (pintype "bidirectional"))
    )
    (net (code "91") (name "Net-(Y1-EN)") (class "Default")
      (node (ref "R29") (pin "P$1") (pinfunction "P$1_P$1") (pintype "passive"))
      (node (ref "Y1") (pin "P1") (pinfunction "EN_P1") (pintype "input"))
    )
    (net (code "92") (name "POT_ADC") (class "Default")
      (node (ref "U5") (pin "2") (pinfunction "Z_2") (pintype "passive"))
      (node (ref "U6") (pin "2") (pinfunction "Z_2") (pintype "passive"))
      (node (ref "U7") (pin "2") (pinfunction "Z_2") (pintype "passive"))
      (node (ref "U8") (pin "3") (pinfunction "AIN_3") (pintype "bidirectional"))
    )
    (net (code "93") (name "POT_CLK") (class "Default")
      (node (ref "JP11") (pin "3") (pinfunction "3_3") (pintype "passive"))
      (node (ref "JP12") (pin "3") (pinfunction "3_3") (pintype "passive"))
      (node (ref "U1") (pin "A3") (pinfunction "PT6A_A3") (pintype "bidirectional"))
      (node (ref "U9") (pin "8") (pinfunction "CLK_8") (pintype "bidirectional"))
    )
    (net (code "94") (name "POT_RST") (class "Default")
      (node (ref "R24") (pin "P$2") (pinfunction "P$2_P$2") (pintype "passive"))
      (node (ref "U9") (pin "6") (pinfunction "QD_6") (pintype "bidirectional"))
      (node (ref "U9") (pin "9") (pinfunction "RST_9") (pintype "bidirectional"))
    )
    (net (code "95") (name "POT_SCL") (class "Default")
      (node (ref "JP11") (pin "4") (pinfunction "4_4") (pintype "passive"))
      (node (ref "JP12") (pin "4") (pinfunction "4_4") (pintype "passive"))
      (node (ref "R51") (pin "P$1") (pinfunction "P$1_P$1") (pintype "passive"))
      (node (ref "U1") (pin "A2") (pinfunction "PT3B_A2") (pintype "bidirectional"))
      (node (ref "U8") (pin "5") (pinfunction "SCL_5") (pintype "bidirectional"))
    )
    (net (code "96") (name "POT_SDA1") (class "Default")
      (node (ref "JP12") (pin "5") (pinfunction "5_5") (pintype "passive"))
      (node (ref "R50") (pin "P$1") (pinfunction "P$1_P$1") (pintype "passive"))
      (node (ref "U1") (pin "D7") (pinfunction "PT10A_D7") (pintype "bidirectional"))
      (node (ref "U8") (pin "4") (pinfunction "SDA_4") (pintype "bidirectional"))
    )
    (net (code "97") (name "POT_SDA2") (class "Default")
      (node (ref "JP11") (pin "5") (pinfunction "5_5") (pintype "passive"))
      (node (ref "JP12") (pin "6") (pinfunction "6_6") (pintype "passive"))
      (node (ref "R48") (pin "P$1") (pinfunction "P$1_P$1") (pintype "passive"))
      (node (ref "U1") (pin "D6") (pinfunction "PT7A_D6") (pintype "bidirectional"))
    )
    (net (code "98") (name "POT_SDA3") (class "Default")
      (node (ref "JP11") (pin "6") (pinfunction "6_6") (pintype "passive"))
      (node (ref "JP12") (pin "7") (pinfunction "7_7") (pintype "passive"))
      (node (ref "R49") (pin "P$1") (pinfunction "P$1_P$1") (pintype "passive"))
      (node (ref "U1") (pin "D5") (pinfunction "PT6B_D5") (pintype "bidirectional"))
    )
    (net (code "99") (name "POT_SEL_1") (class "Default")
      (node (ref "R23") (pin "P$2") (pinfunction "P$2_P$2") (pintype "passive"))
      (node (ref "R25") (pin "P$1") (pinfunction "P$1_P$1") (pintype "passive"))
      (node (ref "R27") (pin "P$2") (pinfunction "P$2_P$2") (pintype "passive"))
      (node (ref "U5") (pin "4") (pinfunction "E_4") (pintype "passive"))
    )
    (net (code "100") (name "POT_SEL_2") (class "Default")
      (node (ref "R21") (pin "P$1") (pinfunction "P$1_P$1") (pintype "passive"))
      (node (ref "R28") (pin "P$1") (pinfunction "P$1_P$1") (pintype "passive"))
      (node (ref "U6") (pin "4") (pinfunction "E_4") (pintype "passive"))
      (node (ref "U9") (pin "3") (pinfunction "QA_3") (pintype "bidirectional"))
    )
    (net (code "101") (name "POT_SEL_3") (class "Default")
      (node (ref "R22") (pin "P$1") (pinfunction "P$1_P$1") (pintype "passive"))
      (node (ref "U7") (pin "4") (pinfunction "E_4") (pintype "passive"))
      (node (ref "U9") (pin "4") (pinfunction "QB_4") (pintype "bidirectional"))
    )
    (net (code "102") (name "POT_SHIFT_IN") (class "Default")
      (node (ref "Q36") (pin "3") (pinfunction "C_3") (pintype "passive"))
      (node (ref "Q37") (pin "3") (pinfunction "C_3") (pintype "passive"))
      (node (ref "Q38") (pin "3") (pinfunction "C_3") (pintype "passive"))
      (node (ref "R20") (pin "P$1") (pinfunction "P$1_P$1") (pintype "passive"))
      (node (ref "R26") (pin "P$1") (pinfunction "P$1_P$1") (pintype "passive"))
      (node (ref "U9") (pin "2") (pinfunction "A2_2") (pintype "bidirectional"))
    )
    (net (code "103") (name "PROGRAMN") (class "Default")
      (node (ref "R34") (pin "P$1") (pinfunction "P$1_P$1") (pintype "passive"))
      (node (ref "U1") (pin "C2") (pinfunction "PROGRAMN_C2") (pintype "bidirectional"))
    )
    (net (code "104") (name "SLEEPN") (class "Default")
      (node (ref "R33") (pin "P$1") (pinfunction "P$1_P$1") (pintype "passive"))
      (node (ref "U1") (pin "P4") (pinfunction "SLEEPN/TOE_P4") (pintype "bidirectional"))
    )
    (net (code "105") (name "STEPPER_1A") (class "Default")
      (node (ref "D1") (pin "1") (pinfunction "IN_1") (pintype "passive"))
      (node (ref "D2") (pin "2") (pinfunction "OUT_2") (pintype "passive"))
      (node (ref "JP1") (pin "1") (pinfunction "1_1") (pintype "passive"))
      (node (ref "Q1") (pin "2") (pinfunction "E_2") (pintype "passive"))
      (node (ref "Q2") (pin "2") (pinfunction "E_2") (pintype "passive"))
    )
    (net (code "106") (name "STEPPER_1AN") (class "Default")
      (node (ref "Q2") (pin "1") (pinfunction "B_1") (pintype "passive"))
      (node (ref "U1") (pin "N3") (pinfunction "PL26B_N3") (pintype "bidirectional"))
    )
    (net (code "107") (name "STEPPER_1AP") (class "Default")
      (node (ref "Q1") (pin "1") (pinfunction "B_1") (pintype "passive"))
      (node (ref "U1") (pin "D3") (pinfunction "PL3B_D3") (pintype "bidirectional"))
    )
    (net (code "108") (name "STEPPER_1B") (class "Default")
      (node (ref "D3") (pin "1") (pinfunction "IN_1") (pintype "passive"))
      (node (ref "D4") (pin "2") (pinfunction "OUT_2") (pintype "passive"))
      (node (ref "JP1") (pin "2") (pinfunction "2_2") (pintype "passive"))
      (node (ref "Q3") (pin "2") (pinfunction "E_2") (pintype "passive"))
      (node (ref "Q4") (pin "2") (pinfunction "E_2") (pintype "passive"))
    )
    (net (code "109") (name "STEPPER_1BN") (class "Default")
      (node (ref "Q4") (pin "1") (pinfunction "B_1") (pintype "passive"))
      (node (ref "U1") (pin "P2") (pinfunction "PL24B_P2") (pintype "bidirectional"))
    )
    (net (code "110") (name "STEPPER_1BP") (class "Default")
      (node (ref "Q3") (pin "1") (pinfunction "B_1") (pintype "passive"))
      (node (ref "U1") (pin "D1") (pinfunction "PL2A_D1") (pintype "bidirectional"))
    )
    (net (code "111") (name "STEPPER_1C") (class "Default")
      (node (ref "D5") (pin "1") (pinfunction "IN_1") (pintype "passive"))
      (node (ref "D6") (pin "2") (pinfunction "OUT_2") (pintype "passive"))
      (node (ref "JP1") (pin "3") (pinfunction "3_3") (pintype "passive"))
      (node (ref "Q5") (pin "2") (pinfunction "E_2") (pintype "passive"))
      (node (ref "Q6") (pin "2") (pinfunction "E_2") (pintype "passive"))
    )
    (net (code "112") (name "STEPPER_1CN") (class "Default")
      (node (ref "Q6") (pin "1") (pinfunction "B_1") (pintype "passive"))
      (node (ref "U1") (pin "P1") (pinfunction "PL24A_P1") (pintype "bidirectional"))
    )
    (net (code "113") (name "STEPPER_1CP") (class "Default")
      (node (ref "Q5") (pin "1") (pinfunction "B_1") (pintype "passive"))
      (node (ref "U1") (pin "D2") (pinfunction "PL3A_D2") (pintype "bidirectional"))
    )
    (net (code "114") (name "STEPPER_1D") (class "Default")
      (node (ref "D7") (pin "1") (pinfunction "IN_1") (pintype "passive"))
      (node (ref "D8") (pin "2") (pinfunction "OUT_2") (pintype "passive"))
      (node (ref "JP1") (pin "4") (pinfunction "4_4") (pintype "passive"))
      (node (ref "Q7") (pin "2") (pinfunction "E_2") (pintype "passive"))
      (node (ref "Q8") (pin "2") (pinfunction "E_2") (pintype "passive"))
    )
    (net (code "115") (name "STEPPER_1DN") (class "Default")
      (node (ref "Q8") (pin "1") (pinfunction "B_1") (pintype "passive"))
      (node (ref "U1") (pin "N2") (pinfunction "PL21B_N2") (pintype "bidirectional"))
    )
    (net (code "116") (name "STEPPER_1DP") (class "Default")
      (node (ref "Q7") (pin "1") (pinfunction "B_1") (pintype "passive"))
      (node (ref "U1") (pin "E1") (pinfunction "PL7A_E1") (pintype "bidirectional"))
    )
    (net (code "117") (name "STEPPER_2A") (class "Default")
      (node (ref "D10") (pin "2") (pinfunction "OUT_2") (pintype "passive"))
      (node (ref "D9") (pin "1") (pinfunction "IN_1") (pintype "passive"))
      (node (ref "JP2") (pin "1") (pinfunction "1_1") (pintype "passive"))
      (node (ref "Q10") (pin "2") (pinfunction "E_2") (pintype "passive"))
      (node (ref "Q9") (pin "2") (pinfunction "E_2") (pintype "passive"))
    )
    (net (code "118") (name "STEPPER_2AN") (class "Default")
      (node (ref "Q10") (pin "1") (pinfunction "B_1") (pintype "passive"))
      (node (ref "U1") (pin "N1") (pinfunction "PL23B_N1") (pintype "bidirectional"))
    )
    (net (code "119") (name "STEPPER_2AP") (class "Default")
      (node (ref "Q9") (pin "1") (pinfunction "B_1") (pintype "passive"))
      (node (ref "U1") (pin "E2") (pinfunction "PL5A_E2") (pintype "bidirectional"))
    )
    (net (code "120") (name "STEPPER_2B") (class "Default")
      (node (ref "D11") (pin "1") (pinfunction "IN_1") (pintype "passive"))
      (node (ref "D12") (pin "2") (pinfunction "OUT_2") (pintype "passive"))
      (node (ref "JP2") (pin "2") (pinfunction "2_2") (pintype "passive"))
      (node (ref "Q11") (pin "2") (pinfunction "E_2") (pintype "passive"))
      (node (ref "Q12") (pin "2") (pinfunction "E_2") (pintype "passive"))
    )
    (net (code "121") (name "STEPPER_2BN") (class "Default")
      (node (ref "Q12") (pin "1") (pinfunction "B_1") (pintype "passive"))
      (node (ref "U1") (pin "M2") (pinfunction "PL18B_M2") (pintype "bidirectional"))
    )
    (net (code "122") (name "STEPPER_2BP") (class "Default")
      (node (ref "Q11") (pin "1") (pinfunction "B_1") (pintype "passive"))
      (node (ref "U1") (pin "F1") (pinfunction "PL7B_F1") (pintype "bidirectional"))
    )
    (net (code "123") (name "STEPPER_2C") (class "Default")
      (node (ref "D13") (pin "1") (pinfunction "IN_1") (pintype "passive"))
      (node (ref "D14") (pin "2") (pinfunction "OUT_2") (pintype "passive"))
      (node (ref "JP2") (pin "3") (pinfunction "3_3") (pintype "passive"))
      (node (ref "Q13") (pin "2") (pinfunction "E_2") (pintype "passive"))
      (node (ref "Q14") (pin "2") (pinfunction "E_2") (pintype "passive"))
    )
    (net (code "124") (name "STEPPER_2CN") (class "Default")
      (node (ref "Q14") (pin "1") (pinfunction "B_1") (pintype "passive"))
      (node (ref "U1") (pin "M1") (pinfunction "PL18A_M1") (pintype "bidirectional"))
    )
    (net (code "125") (name "STEPPER_2CP") (class "Default")
      (node (ref "Q13") (pin "1") (pinfunction "B_1") (pintype "passive"))
      (node (ref "U1") (pin "F2") (pinfunction "PL4B_F2") (pintype "bidirectional"))
    )
    (net (code "126") (name "STEPPER_2D") (class "Default")
      (node (ref "D15") (pin "1") (pinfunction "IN_1") (pintype "passive"))
      (node (ref "D16") (pin "2") (pinfunction "OUT_2") (pintype "passive"))
      (node (ref "JP2") (pin "4") (pinfunction "4_4") (pintype "passive"))
      (node (ref "Q15") (pin "2") (pinfunction "E_2") (pintype "passive"))
      (node (ref "Q16") (pin "2") (pinfunction "E_2") (pintype "passive"))
    )
    (net (code "127") (name "STEPPER_2DN") (class "Default")
      (node (ref "Q16") (pin "1") (pinfunction "B_1") (pintype "passive"))
      (node (ref "U1") (pin "L2") (pinfunction "PL16B_L2") (pintype "bidirectional"))
    )
    (net (code "128") (name "STEPPER_2DP") (class "Default")
      (node (ref "Q15") (pin "1") (pinfunction "B_1") (pintype "passive"))
      (node (ref "U1") (pin "G1") (pinfunction "PL2B_G1") (pintype "bidirectional"))
    )
    (net (code "129") (name "STEPPER_3A") (class "Default")
      (node (ref "D17") (pin "1") (pinfunction "IN_1") (pintype "passive"))
      (node (ref "D18") (pin "2") (pinfunction "OUT_2") (pintype "passive"))
      (node (ref "JP3") (pin "1") (pinfunction "1_1") (pintype "passive"))
      (node (ref "Q17") (pin "2") (pinfunction "E_2") (pintype "passive"))
      (node (ref "Q18") (pin "2") (pinfunction "E_2") (pintype "passive"))
    )
    (net (code "130") (name "STEPPER_3AN") (class "Default")
      (node (ref "Q18") (pin "1") (pinfunction "B_1") (pintype "passive"))
      (node (ref "U1") (pin "L1") (pinfunction "PL16A_L1") (pintype "bidirectional"))
    )
    (net (code "131") (name "STEPPER_3AP") (class "Default")
      (node (ref "Q17") (pin "1") (pinfunction "B_1") (pintype "passive"))
      (node (ref "U1") (pin "G2") (pinfunction "PL8B_G2") (pintype "bidirectional"))
    )
    (net (code "132") (name "STEPPER_3B") (class "Default")
      (node (ref "D19") (pin "1") (pinfunction "IN_1") (pintype "passive"))
      (node (ref "D20") (pin "2") (pinfunction "OUT_2") (pintype "passive"))
      (node (ref "JP3") (pin "2") (pinfunction "2_2") (pintype "passive"))
      (node (ref "Q19") (pin "2") (pinfunction "E_2") (pintype "passive"))
      (node (ref "Q20") (pin "2") (pinfunction "E_2") (pintype "passive"))
    )
    (net (code "133") (name "STEPPER_3BN") (class "Default")
      (node (ref "Q20") (pin "1") (pinfunction "B_1") (pintype "passive"))
      (node (ref "U1") (pin "K2") (pinfunction "PL17B_K2") (pintype "bidirectional"))
    )
    (net (code "134") (name "STEPPER_3BP") (class "Default")
      (node (ref "Q19") (pin "1") (pinfunction "B_1") (pintype "passive"))
      (node (ref "U1") (pin "H1") (pinfunction "PL9A_H1") (pintype "bidirectional"))
    )
    (net (code "135") (name "STEPPER_3C") (class "Default")
      (node (ref "D21") (pin "1") (pinfunction "IN_1") (pintype "passive"))
      (node (ref "D22") (pin "2") (pinfunction "OUT_2") (pintype "passive"))
      (node (ref "JP3") (pin "3") (pinfunction "3_3") (pintype "passive"))
      (node (ref "Q21") (pin "2") (pinfunction "E_2") (pintype "passive"))
      (node (ref "Q22") (pin "2") (pinfunction "E_2") (pintype "passive"))
    )
    (net (code "136") (name "STEPPER_3CN") (class "Default")
      (node (ref "Q22") (pin "1") (pinfunction "B_1") (pintype "passive"))
      (node (ref "U1") (pin "K1") (pinfunction "PL17A_K1") (pintype "bidirectional"))
    )
    (net (code "137") (name "STEPPER_3CP") (class "Default")
      (node (ref "Q21") (pin "1") (pinfunction "B_1") (pintype "passive"))
      (node (ref "U1") (pin "H2") (pinfunction "PL9B_H2") (pintype "bidirectional"))
    )
    (net (code "138") (name "STEPPER_3D") (class "Default")
      (node (ref "D23") (pin "1") (pinfunction "IN_1") (pintype "passive"))
      (node (ref "D24") (pin "2") (pinfunction "OUT_2") (pintype "passive"))
      (node (ref "JP3") (pin "4") (pinfunction "4_4") (pintype "passive"))
      (node (ref "Q23") (pin "2") (pinfunction "E_2") (pintype "passive"))
      (node (ref "Q24") (pin "2") (pinfunction "E_2") (pintype "passive"))
    )
    (net (code "139") (name "STEPPER_3DN") (class "Default")
      (node (ref "Q24") (pin "1") (pinfunction "B_1") (pintype "passive"))
      (node (ref "U1") (pin "J2") (pinfunction "PL11B_J2") (pintype "bidirectional"))
    )
    (net (code "140") (name "STEPPER_3DP") (class "Default")
      (node (ref "Q23") (pin "1") (pinfunction "B_1") (pintype "passive"))
      (node (ref "U1") (pin "J1") (pinfunction "PL11A_J1") (pintype "bidirectional"))
    )
    (net (code "141") (name "STEPPER_PWR") (class "Default")
      (node (ref "C1") (pin "P$2") (pinfunction "P$2_P$2") (pintype "passive"))
      (node (ref "C10") (pin "P$2") (pinfunction "P$2_P$2") (pintype "passive"))
      (node (ref "C11") (pin "P$2") (pinfunction "P$2_P$2") (pintype "passive"))
      (node (ref "C12") (pin "P$2") (pinfunction "P$2_P$2") (pintype "passive"))
      (node (ref "C2") (pin "P$2") (pinfunction "P$2_P$2") (pintype "passive"))
      (node (ref "C3") (pin "P$2") (pinfunction "P$2_P$2") (pintype "passive"))
      (node (ref "C4") (pin "P$2") (pinfunction "P$2_P$2") (pintype "passive"))
      (node (ref "C5") (pin "P$2") (pinfunction "P$2_P$2") (pintype "passive"))
      (node (ref "C6") (pin "P$2") (pinfunction "P$2_P$2") (pintype "passive"))
      (node (ref "C7") (pin "P$2") (pinfunction "P$2_P$2") (pintype "passive"))
      (node (ref "C8") (pin "P$2") (pinfunction "P$2_P$2") (pintype "passive"))
      (node (ref "C9") (pin "P$2") (pinfunction "P$2_P$2") (pintype "passive"))
      (node (ref "D1") (pin "2") (pinfunction "OUT_2") (pintype "passive"))
      (node (ref "D11") (pin "2") (pinfunction "OUT_2") (pintype "passive"))
      (node (ref "D13") (pin "2") (pinfunction "OUT_2") (pintype "passive"))
      (node (ref "D15") (pin "2") (pinfunction "OUT_2") (pintype "passive"))
      (node (ref "D17") (pin "2") (pinfunction "OUT_2") (pintype "passive"))
      (node (ref "D19") (pin "2") (pinfunction "OUT_2") (pintype "passive"))
      (node (ref "D21") (pin "2") (pinfunction "OUT_2") (pintype "passive"))
      (node (ref "D23") (pin "2") (pinfunction "OUT_2") (pintype "passive"))
      (node (ref "D3") (pin "2") (pinfunction "OUT_2") (pintype "passive"))
      (node (ref "D5") (pin "2") (pinfunction "OUT_2") (pintype "passive"))
      (node (ref "D7") (pin "2") (pinfunction "OUT_2") (pintype "passive"))
      (node (ref "D9") (pin "2") (pinfunction "OUT_2") (pintype "passive"))
      (node (ref "JP15") (pin "1") (pinfunction "1_1") (pintype "passive"))
      (node (ref "Q1") (pin "3") (pinfunction "C_3") (pintype "passive"))
      (node (ref "Q11") (pin "3") (pinfunction "C_3") (pintype "passive"))
      (node (ref "Q13") (pin "3") (pinfunction "C_3") (pintype "passive"))
      (node (ref "Q15") (pin "3") (pinfunction "C_3") (pintype "passive"))
      (node (ref "Q17") (pin "3") (pinfunction "C_3") (pintype "passive"))
      (node (ref "Q19") (pin "3") (pinfunction "C_3") (pintype "passive"))
      (node (ref "Q21") (pin "3") (pinfunction "C_3") (pintype "passive"))
      (node (ref "Q23") (pin "3") (pinfunction "C_3") (pintype "passive"))
      (node (ref "Q3") (pin "3") (pinfunction "C_3") (pintype "passive"))
      (node (ref "Q5") (pin "3") (pinfunction "C_3") (pintype "passive"))
      (node (ref "Q7") (pin "3") (pinfunction "C_3") (pintype "passive"))
      (node (ref "Q9") (pin "3") (pinfunction "C_3") (pintype "passive"))
      (node (ref "R38") (pin "P$2") (pinfunction "P$2_P$2") (pintype "passive"))
    )
    (net (code "142") (name "TCK") (class "Default")
      (node (ref "JP14") (pin "6") (pinfunction "6_6") (pintype "passive"))
      (node (ref "U1") (pin "B14") (pinfunction "TCK_B14") (pintype "bidirectional"))
    )
    (net (code "143") (name "TDI") (class "Default")
      (node (ref "JP14") (pin "3") (pinfunction "3_3") (pintype "passive"))
      (node (ref "U1") (pin "D14") (pinfunction "TDI_D14") (pintype "bidirectional"))
    )
    (net (code "144") (name "TDO") (class "Default")
      (node (ref "JP14") (pin "4") (pinfunction "4_4") (pintype "passive"))
      (node (ref "U1") (pin "E16") (pinfunction "TDO_E16") (pintype "bidirectional"))
    )
    (net (code "145") (name "THERMO_SCL") (class "Default")
      (node (ref "JP25") (pin "1") (pinfunction "1_1") (pintype "passive"))
      (node (ref "JP26") (pin "1") (pinfunction "1_1") (pintype "passive"))
      (node (ref "R46") (pin "P$1") (pinfunction "P$1_P$1") (pintype "passive"))
      (node (ref "U1") (pin "B7") (pinfunction "PT14B_B7") (pintype "bidirectional"))
      (node (ref "U16") (pin "5") (pinfunction "SCL_5") (pintype "bidirectional"))
    )
    (net (code "146") (name "THERMO_SDA1") (class "Default")
      (node (ref "JP26") (pin "2") (pinfunction "2_2") (pintype "passive"))
      (node (ref "R45") (pin "P$1") (pinfunction "P$1_P$1") (pintype "passive"))
      (node (ref "U1") (pin "A8") (pinfunction "PT15B_A8") (pintype "bidirectional"))
      (node (ref "U16") (pin "4") (pinfunction "SDA_4") (pintype "bidirectional"))
    )
    (net (code "147") (name "THERMO_SDA2") (class "Default")
      (node (ref "JP25") (pin "2") (pinfunction "2_2") (pintype "passive"))
      (node (ref "R47") (pin "P$1") (pinfunction "P$1_P$1") (pintype "passive"))
      (node (ref "U1") (pin "A7") (pinfunction "PT15A_A7") (pintype "bidirectional"))
    )
    (net (code "148") (name "TMS") (class "Default")
      (node (ref "JP14") (pin "1") (pinfunction "1_1") (pintype "passive"))
      (node (ref "U1") (pin "C14") (pinfunction "TMS_C14") (pintype "bidirectional"))
    )
    (net (code "149") (name "unconnected-(JP14-Pad2)") (class "Default")
      (node (ref "JP14") (pin "2") (pinfunction "2_2") (pintype "passive"))
    )
    (net (code "150") (name "unconnected-(U1A-PB2A-PadR4)") (class "Default")
      (node (ref "U1") (pin "R4") (pinfunction "PB2A_R4") (pintype "bidirectional"))
    )
    (net (code "151") (name "unconnected-(U1A-PB2B-PadN5)") (class "Default")
      (node (ref "U1") (pin "N5") (pinfunction "PB2B_N5") (pintype "bidirectional"))
    )
    (net (code "152") (name "unconnected-(U1A-PB3A-PadM7)") (class "Default")
      (node (ref "U1") (pin "M7") (pinfunction "PB3A_M7") (pintype "bidirectional"))
    )
    (net (code "153") (name "unconnected-(U1A-PB3B-PadR1)") (class "Default")
      (node (ref "U1") (pin "R1") (pinfunction "PB3B_R1") (pintype "bidirectional"))
    )
    (net (code "154") (name "unconnected-(U1A-PB4A-PadN6)") (class "Default")
      (node (ref "U1") (pin "N6") (pinfunction "PB4A_N6") (pintype "bidirectional"))
    )
    (net (code "155") (name "unconnected-(U1A-PB5B-PadP5)") (class "Default")
      (node (ref "U1") (pin "P5") (pinfunction "PB5B_P5") (pintype "bidirectional"))
    )
    (net (code "156") (name "unconnected-(U1A-PB8A-PadT4)") (class "Default")
      (node (ref "U1") (pin "T4") (pinfunction "PB8A_T4") (pintype "bidirectional"))
    )
    (net (code "157") (name "unconnected-(U1A-PB8B-PadR5)") (class "Default")
      (node (ref "U1") (pin "R5") (pinfunction "PB8B_R5") (pintype "bidirectional"))
    )
    (net (code "158") (name "unconnected-(U1A-PB9B-PadM8)") (class "Default")
      (node (ref "U1") (pin "M8") (pinfunction "PB9B_M8") (pintype "bidirectional"))
    )
    (net (code "159") (name "unconnected-(U1A-PB10A-PadT5)") (class "Default")
      (node (ref "U1") (pin "T5") (pinfunction "PB10A_T5") (pintype "bidirectional"))
    )
    (net (code "160") (name "unconnected-(U1A-PB10B-PadP6)") (class "Default")
      (node (ref "U1") (pin "P6") (pinfunction "PB10B_P6") (pintype "bidirectional"))
    )
    (net (code "161") (name "unconnected-(U1A-PB12A-PadP7)") (class "Default")
      (node (ref "U1") (pin "P7") (pinfunction "PB12A_P7") (pintype "bidirectional"))
    )
    (net (code "162") (name "unconnected-(U1A-PB13B-PadN8)") (class "Default")
      (node (ref "U1") (pin "N8") (pinfunction "PB13B_N8") (pintype "bidirectional"))
    )
    (net (code "163") (name "unconnected-(U1A-PB14A-PadR7)") (class "Default")
      (node (ref "U1") (pin "R7") (pinfunction "PB14A_R7") (pintype "bidirectional"))
    )
    (net (code "164") (name "unconnected-(U1A-PB14B-PadT7)") (class "Default")
      (node (ref "U1") (pin "T7") (pinfunction "PB14B_T7") (pintype "bidirectional"))
    )
    (net (code "165") (name "unconnected-(U1A-PB15B-PadT8)") (class "Default")
      (node (ref "U1") (pin "T8") (pinfunction "PB15B_T8") (pintype "bidirectional"))
    )
    (net (code "166") (name "unconnected-(U1A-PB16A-PadR8)") (class "Default")
      (node (ref "U1") (pin "R8") (pinfunction "PB16A_R8") (pintype "bidirectional"))
    )
    (net (code "167") (name "unconnected-(U1A-PB16B-PadT9)") (class "Default")
      (node (ref "U1") (pin "T9") (pinfunction "PB16B_T9") (pintype "bidirectional"))
    )
    (net (code "168") (name "unconnected-(U1A-PB17A-PadR9)") (class "Default")
      (node (ref "U1") (pin "R9") (pinfunction "PB17A_R9") (pintype "bidirectional"))
    )
    (net (code "169") (name "unconnected-(U1A-PB17B-PadP9)") (class "Default")
      (node (ref "U1") (pin "P9") (pinfunction "PB17B_P9") (pintype "bidirectional"))
    )
    (net (code "170") (name "unconnected-(U1A-PB19A-PadR10)") (class "Default")
      (node (ref "U1") (pin "R10") (pinfunction "PB19A_R10") (pintype "bidirectional"))
    )
    (net (code "171") (name "unconnected-(U1A-PB19B-PadP10)") (class "Default")
      (node (ref "U1") (pin "P10") (pinfunction "PB19B_P10") (pintype "bidirectional"))
    )
    (net (code "172") (name "unconnected-(U1A-PB20A-PadN9)") (class "Default")
      (node (ref "U1") (pin "N9") (pinfunction "PB20A_N9") (pintype "bidirectional"))
    )
    (net (code "173") (name "unconnected-(U1A-PB21B-PadM9)") (class "Default")
      (node (ref "U1") (pin "M9") (pinfunction "PB21B_M9") (pintype "bidirectional"))
    )
    (net (code "174") (name "unconnected-(U1A-PB22A-PadR12)") (class "Default")
      (node (ref "U1") (pin "R12") (pinfunction "PB22A_R12") (pintype "bidirectional"))
    )
    (net (code "175") (name "unconnected-(U1A-PB22B-PadT12)") (class "Default")
      (node (ref "U1") (pin "T12") (pinfunction "PB22B_T12") (pintype "bidirectional"))
    )
    (net (code "176") (name "unconnected-(U1A-PB23A-PadP13)") (class "Default")
      (node (ref "U1") (pin "P13") (pinfunction "PB23A_P13") (pintype "bidirectional"))
    )
    (net (code "177") (name "unconnected-(U1A-PB23B-PadR13)") (class "Default")
      (node (ref "U1") (pin "R13") (pinfunction "PB23B_R13") (pintype "bidirectional"))
    )
    (net (code "178") (name "unconnected-(U1A-PB24A-PadM11)") (class "Default")
      (node (ref "U1") (pin "M11") (pinfunction "PB24A_M11") (pintype "bidirectional"))
    )
    (net (code "179") (name "unconnected-(U1A-PB24B-PadN11)") (class "Default")
      (node (ref "U1") (pin "N11") (pinfunction "PB24B_N11") (pintype "bidirectional"))
    )
    (net (code "180") (name "unconnected-(U1A-PB25A-PadN10)") (class "Default")
      (node (ref "U1") (pin "N10") (pinfunction "PB25A_N10") (pintype "bidirectional"))
    )
    (net (code "181") (name "unconnected-(U1A-PB25B-PadM10)") (class "Default")
      (node (ref "U1") (pin "M10") (pinfunction "PB25B_M10") (pintype "bidirectional"))
    )
    (net (code "182") (name "unconnected-(U1A-PB26A-PadT13)") (class "Default")
      (node (ref "U1") (pin "T13") (pinfunction "PB26A_T13") (pintype "bidirectional"))
    )
    (net (code "183") (name "unconnected-(U1A-PB26B-PadP14)") (class "Default")
      (node (ref "U1") (pin "P14") (pinfunction "PB26B_P14") (pintype "bidirectional"))
    )
    (net (code "184") (name "unconnected-(U1A-PB27A-PadR11)") (class "Default")
      (node (ref "U1") (pin "R11") (pinfunction "PB27A_R11") (pintype "bidirectional"))
    )
    (net (code "185") (name "unconnected-(U1A-PB27B-PadP12)") (class "Default")
      (node (ref "U1") (pin "P12") (pinfunction "PB27B_P12") (pintype "bidirectional"))
    )
    (net (code "186") (name "unconnected-(U1A-PB28A-PadT14)") (class "Default")
      (node (ref "U1") (pin "T14") (pinfunction "PB28A_T14") (pintype "bidirectional"))
    )
    (net (code "187") (name "unconnected-(U1A-PB29B-PadR14)") (class "Default")
      (node (ref "U1") (pin "R14") (pinfunction "PB29B_R14") (pintype "bidirectional"))
    )
    (net (code "188") (name "unconnected-(U1A-PB30A-PadP11)") (class "Default")
      (node (ref "U1") (pin "P11") (pinfunction "PB30A_P11") (pintype "bidirectional"))
    )
    (net (code "189") (name "unconnected-(U1A-PB30B-PadN12)") (class "Default")
      (node (ref "U1") (pin "N12") (pinfunction "PB30B_N12") (pintype "bidirectional"))
    )
    (net (code "190") (name "unconnected-(U1B-PL4A-PadF3)") (class "Default")
      (node (ref "U1") (pin "F3") (pinfunction "PL4A_F3") (pintype "bidirectional"))
    )
    (net (code "191") (name "unconnected-(U1B-PL6B-PadG4)") (class "Default")
      (node (ref "U1") (pin "G4") (pinfunction "PL6B_G4") (pintype "bidirectional"))
    )
    (net (code "192") (name "unconnected-(U1B-PL8A-PadG3)") (class "Default")
      (node (ref "U1") (pin "G3") (pinfunction "PL8A_G3") (pintype "bidirectional"))
    )
    (net (code "193") (name "unconnected-(U1B-PL12A-PadE3)") (class "Default")
      (node (ref "U1") (pin "E3") (pinfunction "PL12A_E3") (pintype "bidirectional"))
    )
    (net (code "194") (name "unconnected-(U1B-PL12B-PadF4)") (class "Default")
      (node (ref "U1") (pin "F4") (pinfunction "PL12B_F4") (pintype "bidirectional"))
    )
    (net (code "195") (name "unconnected-(U1B-PL13A-PadH3)") (class "Default")
      (node (ref "U1") (pin "H3") (pinfunction "PL13A_H3") (pintype "bidirectional"))
    )
    (net (code "196") (name "unconnected-(U1B-PL13B-PadJ3)") (class "Default")
      (node (ref "U1") (pin "J3") (pinfunction "PL13B_J3") (pintype "bidirectional"))
    )
    (net (code "197") (name "unconnected-(U1B-PL14A-PadG5)") (class "Default")
      (node (ref "U1") (pin "G5") (pinfunction "PL14A_G5") (pintype "bidirectional"))
    )
    (net (code "198") (name "unconnected-(U1B-PL15B-PadJ4)") (class "Default")
      (node (ref "U1") (pin "J4") (pinfunction "PL15B_J4") (pintype "bidirectional"))
    )
    (net (code "199") (name "unconnected-(U1B-PL19A-PadK3)") (class "Default")
      (node (ref "U1") (pin "K3") (pinfunction "PL19A_K3") (pintype "bidirectional"))
    )
    (net (code "200") (name "unconnected-(U1B-PL19B-PadL3)") (class "Default")
      (node (ref "U1") (pin "L3") (pinfunction "PL19B_L3") (pintype "bidirectional"))
    )
    (net (code "201") (name "unconnected-(U1B-PL20A-PadK4)") (class "Default")
      (node (ref "U1") (pin "K4") (pinfunction "PL20A_K4") (pintype "bidirectional"))
    )
    (net (code "202") (name "unconnected-(U1B-PL20B-PadK5)") (class "Default")
      (node (ref "U1") (pin "K5") (pinfunction "PL20B_K5") (pintype "bidirectional"))
    )
    (net (code "203") (name "unconnected-(U1B-PL21A-PadL4)") (class "Default")
      (node (ref "U1") (pin "L4") (pinfunction "PL21A_L4") (pintype "bidirectional"))
    )
    (net (code "204") (name "unconnected-(U1B-PL22A-PadJ5)") (class "Default")
      (node (ref "U1") (pin "J5") (pinfunction "PL22A_J5") (pintype "bidirectional"))
    )
    (net (code "205") (name "unconnected-(U1B-PL25A-PadL5)") (class "Default")
      (node (ref "U1") (pin "L5") (pinfunction "PL25A_L5") (pintype "bidirectional"))
    )
    (net (code "206") (name "unconnected-(U1B-PL25B-PadM6)") (class "Default")
      (node (ref "U1") (pin "M6") (pinfunction "PL25B_M6") (pintype "bidirectional"))
    )
    (net (code "207") (name "unconnected-(U1B-PL26A-PadM3)") (class "Default")
      (node (ref "U1") (pin "M3") (pinfunction "PL26A_M3") (pintype "bidirectional"))
    )
    (net (code "208") (name "unconnected-(U1C-PR2A-PadG13)") (class "Default")
      (node (ref "U1") (pin "G13") (pinfunction "PR2A_G13") (pintype "bidirectional"))
    )
    (net (code "209") (name "unconnected-(U1C-PR2B-PadH15)") (class "Default")
      (node (ref "U1") (pin "H15") (pinfunction "PR2B_H15") (pintype "bidirectional"))
    )
    (net (code "210") (name "unconnected-(U1C-PR3A-PadC15)") (class "Default")
      (node (ref "U1") (pin "C15") (pinfunction "PR3A_C15") (pintype "bidirectional"))
    )
    (net (code "211") (name "unconnected-(U1C-PR3B-PadD15)") (class "Default")
      (node (ref "U1") (pin "D15") (pinfunction "PR3B_D15") (pintype "bidirectional"))
    )
    (net (code "212") (name "unconnected-(U1C-PR4A-PadE14)") (class "Default")
      (node (ref "U1") (pin "E14") (pinfunction "PR4A_E14") (pintype "bidirectional"))
    )
    (net (code "213") (name "unconnected-(U1C-PR4B-PadF14)") (class "Default")
      (node (ref "U1") (pin "F14") (pinfunction "PR4B_F14") (pintype "bidirectional"))
    )
    (net (code "214") (name "unconnected-(U1C-PR5A-PadE15)") (class "Default")
      (node (ref "U1") (pin "E15") (pinfunction "PR5A_E15") (pintype "bidirectional"))
    )
    (net (code "215") (name "unconnected-(U1C-PR6B-PadH14)") (class "Default")
      (node (ref "U1") (pin "H14") (pinfunction "PR6B_H14") (pintype "bidirectional"))
    )
    (net (code "216") (name "unconnected-(U1C-PR7A-PadC16)") (class "Default")
      (node (ref "U1") (pin "C16") (pinfunction "PR7A_C16") (pintype "bidirectional"))
    )
    (net (code "217") (name "unconnected-(U1C-PR7B-PadB16)") (class "Default")
      (node (ref "U1") (pin "B16") (pinfunction "PR7B_B16") (pintype "bidirectional"))
    )
    (net (code "218") (name "unconnected-(U1C-PR8A-PadF16)") (class "Default")
      (node (ref "U1") (pin "F16") (pinfunction "PR8A_F16") (pintype "bidirectional"))
    )
    (net (code "219") (name "unconnected-(U1C-PR8B-PadG16)") (class "Default")
      (node (ref "U1") (pin "G16") (pinfunction "PR8B_G16") (pintype "bidirectional"))
    )
    (net (code "220") (name "unconnected-(U1C-PR9A-PadF13)") (class "Default")
      (node (ref "U1") (pin "F13") (pinfunction "PR9A_F13") (pintype "bidirectional"))
    )
    (net (code "221") (name "unconnected-(U1C-PR9B-PadG12)") (class "Default")
      (node (ref "U1") (pin "G12") (pinfunction "PR9B_G12") (pintype "bidirectional"))
    )
    (net (code "222") (name "unconnected-(U1C-PR11A-PadG14)") (class "Default")
      (node (ref "U1") (pin "G14") (pinfunction "PR11A_G14") (pintype "bidirectional"))
    )
    (net (code "223") (name "unconnected-(U1C-PR11B-PadG15)") (class "Default")
      (node (ref "U1") (pin "G15") (pinfunction "PR11B_G15") (pintype "bidirectional"))
    )
    (net (code "224") (name "unconnected-(U1C-PR13A-PadH12)") (class "Default")
      (node (ref "U1") (pin "H12") (pinfunction "PR13A_H12") (pintype "bidirectional"))
    )
    (net (code "225") (name "unconnected-(U1C-PR13B-PadH13)") (class "Default")
      (node (ref "U1") (pin "H13") (pinfunction "PR13B_H13") (pintype "bidirectional"))
    )
    (net (code "226") (name "unconnected-(U1C-PR14A-PadF15)") (class "Default")
      (node (ref "U1") (pin "F15") (pinfunction "PR14A_F15") (pintype "bidirectional"))
    )
    (net (code "227") (name "unconnected-(U1C-PR16A-PadJ14)") (class "Default")
      (node (ref "U1") (pin "J14") (pinfunction "PR16A_J14") (pintype "bidirectional"))
    )
    (net (code "228") (name "unconnected-(U1C-PR16B-PadJ15)") (class "Default")
      (node (ref "U1") (pin "J15") (pinfunction "PR16B_J15") (pintype "bidirectional"))
    )
    (net (code "229") (name "unconnected-(U1C-PR17A-PadK12)") (class "Default")
      (node (ref "U1") (pin "K12") (pinfunction "PR17A_K12") (pintype "bidirectional"))
    )
    (net (code "230") (name "unconnected-(U1C-PR17B-PadL12)") (class "Default")
      (node (ref "U1") (pin "L12") (pinfunction "PR17B_L12") (pintype "bidirectional"))
    )
    (net (code "231") (name "unconnected-(U1C-PR19B-PadK14)") (class "Default")
      (node (ref "U1") (pin "K14") (pinfunction "PR19B_K14") (pintype "bidirectional"))
    )
    (net (code "232") (name "unconnected-(U1C-PR21A-PadL14)") (class "Default")
      (node (ref "U1") (pin "L14") (pinfunction "PR21A_L14") (pintype "bidirectional"))
    )
    (net (code "233") (name "unconnected-(U1C-PR22A-PadK13)") (class "Default")
      (node (ref "U1") (pin "K13") (pinfunction "PR22A_K13") (pintype "bidirectional"))
    )
    (net (code "234") (name "unconnected-(U1C-PR23B-PadN14)") (class "Default")
      (node (ref "U1") (pin "N14") (pinfunction "PR23B_N14") (pintype "bidirectional"))
    )
    (net (code "235") (name "unconnected-(U1C-PR25A-PadL13)") (class "Default")
      (node (ref "U1") (pin "L13") (pinfunction "PR25A_L13") (pintype "bidirectional"))
    )
    (net (code "236") (name "unconnected-(U1C-PR25B-PadM14)") (class "Default")
      (node (ref "U1") (pin "M14") (pinfunction "PR25B_M14") (pintype "bidirectional"))
    )
    (net (code "237") (name "unconnected-(U1D-PT2A-PadC5)") (class "Default")
      (node (ref "U1") (pin "C5") (pinfunction "PT2A_C5") (pintype "bidirectional"))
    )
    (net (code "238") (name "unconnected-(U1D-PT2B-PadF5)") (class "Default")
      (node (ref "U1") (pin "F5") (pinfunction "PT2B_F5") (pintype "bidirectional"))
    )
    (net (code "239") (name "unconnected-(U1D-PT3A-PadB1)") (class "Default")
      (node (ref "U1") (pin "B1") (pinfunction "PT3A_B1") (pintype "bidirectional"))
    )
    (net (code "240") (name "unconnected-(U1D-PT4A-PadB2)") (class "Default")
      (node (ref "U1") (pin "B2") (pinfunction "PT4A_B2") (pintype "bidirectional"))
    )
    (net (code "241") (name "unconnected-(U1D-PT5B-PadB3)") (class "Default")
      (node (ref "U1") (pin "B3") (pinfunction "PT5B_B3") (pintype "bidirectional"))
    )
    (net (code "242") (name "unconnected-(U1D-PT7B-PadE6)") (class "Default")
      (node (ref "U1") (pin "E6") (pinfunction "PT7B_E6") (pintype "bidirectional"))
    )
    (net (code "243") (name "unconnected-(U1D-PT10B-PadE7)") (class "Default")
      (node (ref "U1") (pin "E7") (pinfunction "PT10B_E7") (pintype "bidirectional"))
    )
    (net (code "244") (name "unconnected-(U1D-PT11A-PadC6)") (class "Default")
      (node (ref "U1") (pin "C6") (pinfunction "PT11A_C6") (pintype "bidirectional"))
    )
    (net (code "245") (name "unconnected-(U1D-PT12A-PadD8)") (class "Default")
      (node (ref "U1") (pin "D8") (pinfunction "PT12A_D8") (pintype "bidirectional"))
    )
    (net (code "246") (name "unconnected-(U1D-PT13B-PadE8)") (class "Default")
      (node (ref "U1") (pin "E8") (pinfunction "PT13B_E8") (pintype "bidirectional"))
    )
    (net (code "247") (name "unconnected-(U1D-PT14A-PadC7)") (class "Default")
      (node (ref "U1") (pin "C7") (pinfunction "PT14A_C7") (pintype "bidirectional"))
    )
    (net (code "248") (name "unconnected-(U1D-PT16A-PadB8)") (class "Default")
      (node (ref "U1") (pin "B8") (pinfunction "PT16A_B8") (pintype "bidirectional"))
    )
    (net (code "249") (name "unconnected-(U1D-PT16B-PadE9)") (class "Default")
      (node (ref "U1") (pin "E9") (pinfunction "PT16B_E9") (pintype "bidirectional"))
    )
    (net (code "250") (name "unconnected-(U1D-PT17A-PadC8)") (class "Default")
      (node (ref "U1") (pin "C8") (pinfunction "PT17A_C8") (pintype "bidirectional"))
    )
    (net (code "251") (name "unconnected-(U1D-PT17B-PadC9)") (class "Default")
      (node (ref "U1") (pin "C9") (pinfunction "PT17B_C9") (pintype "bidirectional"))
    )
    (net (code "252") (name "unconnected-(U1D-PT18A-PadA9)") (class "Default")
      (node (ref "U1") (pin "A9") (pinfunction "PT18A_A9") (pintype "bidirectional"))
    )
    (net (code "253") (name "unconnected-(U1D-PT18B-PadD10)") (class "Default")
      (node (ref "U1") (pin "D10") (pinfunction "PT18B_D10") (pintype "bidirectional"))
    )
    (net (code "254") (name "unconnected-(U1D-PT19A-PadB10)") (class "Default")
      (node (ref "U1") (pin "B10") (pinfunction "PT19A_B10") (pintype "bidirectional"))
    )
    (net (code "255") (name "unconnected-(U1D-PT19B-PadA10)") (class "Default")
      (node (ref "U1") (pin "A10") (pinfunction "PT19B_A10") (pintype "bidirectional"))
    )
    (net (code "256") (name "unconnected-(U1D-PT20A-PadD9)") (class "Default")
      (node (ref "U1") (pin "D9") (pinfunction "PT20A_D9") (pintype "bidirectional"))
    )
    (net (code "257") (name "unconnected-(U1D-PT21B-PadB9)") (class "Default")
      (node (ref "U1") (pin "B9") (pinfunction "PT21B_B9") (pintype "bidirectional"))
    )
    (net (code "258") (name "unconnected-(U1D-PT22A-PadD11)") (class "Default")
      (node (ref "U1") (pin "D11") (pinfunction "PT22A_D11") (pintype "bidirectional"))
    )
    (net (code "259") (name "unconnected-(U1D-PT22B-PadB11)") (class "Default")
      (node (ref "U1") (pin "B11") (pinfunction "PT22B_B11") (pintype "bidirectional"))
    )
    (net (code "260") (name "unconnected-(U1D-PT23A-PadA11)") (class "Default")
      (node (ref "U1") (pin "A11") (pinfunction "PT23A_A11") (pintype "bidirectional"))
    )
    (net (code "261") (name "unconnected-(U1D-PT23B-PadC12)") (class "Default")
      (node (ref "U1") (pin "C12") (pinfunction "PT23B_C12") (pintype "bidirectional"))
    )
    (net (code "262") (name "unconnected-(U1D-PT24A-PadB12)") (class "Default")
      (node (ref "U1") (pin "B12") (pinfunction "PT24A_B12") (pintype "bidirectional"))
    )
    (net (code "263") (name "unconnected-(U1D-PT25A-PadE10)") (class "Default")
      (node (ref "U1") (pin "E10") (pinfunction "PT25A_E10") (pintype "bidirectional"))
    )
    (net (code "264") (name "unconnected-(U1D-PT25B-PadC10)") (class "Default")
      (node (ref "U1") (pin "C10") (pinfunction "PT25B_C10") (pintype "bidirectional"))
    )
    (net (code "265") (name "unconnected-(U1D-PT27A-PadE11)") (class "Default")
      (node (ref "U1") (pin "E11") (pinfunction "PT27A_E11") (pintype "bidirectional"))
    )
    (net (code "266") (name "unconnected-(U1D-PT30A-PadC11)") (class "Default")
      (node (ref "U1") (pin "C11") (pinfunction "PT30A_C11") (pintype "bidirectional"))
    )
    (net (code "267") (name "unconnected-(U1D-PT30B-PadB13)") (class "Default")
      (node (ref "U1") (pin "B13") (pinfunction "PT30B_B13") (pintype "bidirectional"))
    )
    (net (code "268") (name "unconnected-(U1E-CCLK-PadC1)") (class "Default")
      (node (ref "U1") (pin "C1") (pinfunction "CCLK_C1") (pintype "bidirectional"))
    )
    (net (code "269") (name "unconnected-(U1E-CFG0-PadC4)") (class "Default")
      (node (ref "U1") (pin "C4") (pinfunction "CFG0_C4") (pintype "bidirectional"))
    )
    (net (code "270") (name "unconnected-(U1E-CFG1-PadB4)") (class "Default")
      (node (ref "U1") (pin "B4") (pinfunction "CFG1_B4") (pintype "bidirectional"))
    )
    (net (code "271") (name "unconnected-(U1E-DONE-PadC3)") (class "Default")
      (node (ref "U1") (pin "C3") (pinfunction "DONE_C3") (pintype "bidirectional"))
    )
    (net (code "272") (name "unconnected-(U2-P0A-Pad8)") (class "Default")
      (node (ref "U2") (pin "8") (pinfunction "P0A_8") (pintype "bidirectional"))
    )
    (net (code "273") (name "unconnected-(U2-P1A-Pad7)") (class "Default")
      (node (ref "U2") (pin "7") (pinfunction "P1A_7") (pintype "bidirectional"))
    )
    (net (code "274") (name "unconnected-(U3-P0A-Pad8)") (class "Default")
      (node (ref "U3") (pin "8") (pinfunction "P0A_8") (pintype "bidirectional"))
    )
    (net (code "275") (name "unconnected-(U3-P1A-Pad7)") (class "Default")
      (node (ref "U3") (pin "7") (pinfunction "P1A_7") (pintype "bidirectional"))
    )
    (net (code "276") (name "unconnected-(U4-DNC-Pad3)") (class "Default")
      (node (ref "U4") (pin "3") (pinfunction "DNC_3") (pintype "no_connect"))
    )
    (net (code "277") (name "unconnected-(U4-NC-Pad8)") (class "Default")
      (node (ref "U4") (pin "8") (pinfunction "NC_8") (pintype "no_connect"))
    )
    (net (code "278") (name "unconnected-(U4-NC-Pad13)") (class "Default")
      (node (ref "U4") (pin "13") (pinfunction "NC_13") (pintype "no_connect"))
    )
    (net (code "279") (name "unconnected-(U4-NC-Pad15)") (class "Default")
      (node (ref "U4") (pin "15") (pinfunction "NC_15") (pintype "no_connect"))
    )
    (net (code "280") (name "unconnected-(U4-NC-Pad16)") (class "Default")
      (node (ref "U4") (pin "16") (pinfunction "NC_16") (pintype "no_connect"))
    )
    (net (code "281") (name "unconnected-(U9-QE-Pad10)") (class "Default")
      (node (ref "U9") (pin "10") (pinfunction "QE_10") (pintype "bidirectional"))
    )
    (net (code "282") (name "unconnected-(U9-QF-Pad11)") (class "Default")
      (node (ref "U9") (pin "11") (pinfunction "QF_11") (pintype "bidirectional"))
    )
    (net (code "283") (name "unconnected-(U9-QG-Pad12)") (class "Default")
      (node (ref "U9") (pin "12") (pinfunction "QG_12") (pintype "bidirectional"))
    )
    (net (code "284") (name "unconnected-(U9-QH-Pad13)") (class "Default")
      (node (ref "U9") (pin "13") (pinfunction "QH_13") (pintype "bidirectional"))
    )
    (net (code "285") (name "unconnected-(U10-BCM_4-Pad7)") (class "Default")
      (node (ref "U10") (pin "7") (pinfunction "BCM_4_7") (pintype "bidirectional"))
    )
    (net (code "286") (name "unconnected-(U10-BCM_5-Pad29)") (class "Default")
      (node (ref "U10") (pin "29") (pinfunction "BCM_5_29") (pintype "bidirectional"))
    )
    (net (code "287") (name "unconnected-(U10-BCM_6-Pad31)") (class "Default")
      (node (ref "U10") (pin "31") (pinfunction "BCM_6_31") (pintype "bidirectional"))
    )
    (net (code "288") (name "unconnected-(U10-BCM_12-Pad32)") (class "Default")
      (node (ref "U10") (pin "32") (pinfunction "BCM_12_32") (pintype "bidirectional"))
    )
    (net (code "289") (name "unconnected-(U10-BCM_13-Pad33)") (class "Default")
      (node (ref "U10") (pin "33") (pinfunction "BCM_13_33") (pintype "bidirectional"))
    )
    (net (code "290") (name "unconnected-(U10-BCM_16-Pad36)") (class "Default")
      (node (ref "U10") (pin "36") (pinfunction "BCM_16_36") (pintype "bidirectional"))
    )
    (net (code "291") (name "unconnected-(U10-BCM_17-Pad11)") (class "Default")
      (node (ref "U10") (pin "11") (pinfunction "BCM_17_11") (pintype "bidirectional"))
    )
    (net (code "292") (name "unconnected-(U10-BCM_18-Pad12)") (class "Default")
      (node (ref "U10") (pin "12") (pinfunction "BCM_18_12") (pintype "bidirectional"))
    )
    (net (code "293") (name "unconnected-(U10-BCM_19-Pad35)") (class "Default")
      (node (ref "U10") (pin "35") (pinfunction "BCM_19_35") (pintype "bidirectional"))
    )
    (net (code "294") (name "unconnected-(U10-BCM_20-Pad38)") (class "Default")
      (node (ref "U10") (pin "38") (pinfunction "BCM_20_38") (pintype "bidirectional"))
    )
    (net (code "295") (name "unconnected-(U10-BCM_21-Pad40)") (class "Default")
      (node (ref "U10") (pin "40") (pinfunction "BCM_21_40") (pintype "bidirectional"))
    )
    (net (code "296") (name "unconnected-(U10-BCM_22-Pad15)") (class "Default")
      (node (ref "U10") (pin "15") (pinfunction "BCM_22_15") (pintype "bidirectional"))
    )
    (net (code "297") (name "unconnected-(U10-BCM_23-Pad16)") (class "Default")
      (node (ref "U10") (pin "16") (pinfunction "BCM_23_16") (pintype "bidirectional"))
    )
    (net (code "298") (name "unconnected-(U10-BCM_24-Pad18)") (class "Default")
      (node (ref "U10") (pin "18") (pinfunction "BCM_24_18") (pintype "bidirectional"))
    )
    (net (code "299") (name "unconnected-(U10-BCM_25-Pad22)") (class "Default")
      (node (ref "U10") (pin "22") (pinfunction "BCM_25_22") (pintype "bidirectional"))
    )
    (net (code "300") (name "unconnected-(U10-BCM_26-Pad37)") (class "Default")
      (node (ref "U10") (pin "37") (pinfunction "BCM_26_37") (pintype "bidirectional"))
    )
    (net (code "301") (name "unconnected-(U10-BCM_27-Pad13)") (class "Default")
      (node (ref "U10") (pin "13") (pinfunction "BCM_27_13") (pintype "bidirectional"))
    )
    (net (code "302") (name "unconnected-(U10-CE0-Pad24)") (class "Default")
      (node (ref "U10") (pin "24") (pinfunction "CE0_24") (pintype "bidirectional"))
    )
    (net (code "303") (name "unconnected-(U10-CE1-Pad26)") (class "Default")
      (node (ref "U10") (pin "26") (pinfunction "CE1_26") (pintype "bidirectional"))
    )
    (net (code "304") (name "unconnected-(U10-ID_SCL-Pad28)") (class "Default")
      (node (ref "U10") (pin "28") (pinfunction "ID_SCL_28") (pintype "bidirectional"))
    )
    (net (code "305") (name "unconnected-(U10-ID_SDA-Pad27)") (class "Default")
      (node (ref "U10") (pin "27") (pinfunction "ID_SDA_27") (pintype "bidirectional"))
    )
    (net (code "306") (name "unconnected-(U10-MISO-Pad21)") (class "Default")
      (node (ref "U10") (pin "21") (pinfunction "MISO_21") (pintype "bidirectional"))
    )
    (net (code "307") (name "unconnected-(U10-MOSI-Pad19)") (class "Default")
      (node (ref "U10") (pin "19") (pinfunction "MOSI_19") (pintype "bidirectional"))
    )
    (net (code "308") (name "unconnected-(U10-SCL-Pad5)") (class "Default")
      (node (ref "U10") (pin "5") (pinfunction "SCL_5") (pintype "bidirectional"))
    )
    (net (code "309") (name "unconnected-(U10-SCLK-Pad23)") (class "Default")
      (node (ref "U10") (pin "23") (pinfunction "SCLK_23") (pintype "bidirectional"))
    )
    (net (code "310") (name "unconnected-(U10-SDA-Pad3)") (class "Default")
      (node (ref "U10") (pin "3") (pinfunction "SDA_3") (pintype "bidirectional"))
    )
    (net (code "311") (name "unconnected-(U14-E60.9V{slash}C-Pad1)") (class "Default")
      (node (ref "U14") (pin "1") (pinfunction "E60.9V/C_1") (pintype "passive"))
    )
    (net (code "312") (name "unconnected-(U14-J51.7V{slash}C-Pad8)") (class "Default")
      (node (ref "U14") (pin "8") (pinfunction "J51.7V/C_8") (pintype "passive"))
    )
    (net (code "313") (name "unconnected-(U14-R-Pad6)") (class "Default")
      (node (ref "U14") (pin "6") (pinfunction "R_6") (pintype "passive"))
    )
    (net (code "314") (name "unconnected-(U14-VO10MV{slash}C-Pad3)") (class "Default")
      (node (ref "U14") (pin "3") (pinfunction "VO10MV/C_3") (pintype "passive"))
    )
    (net (code "315") (name "unconnected-(U15-NC-Pad1)") (class "Default")
      (node (ref "U15") (pin "1") (pinfunction "NC_1") (pintype "no_connect"))
    )
    (net (code "316") (name "unconnected-(U15-NC-Pad5)") (class "Default")
      (node (ref "U15") (pin "5") (pinfunction "NC_5") (pintype "no_connect"))
    )
    (net (code "317") (name "unconnected-(U15-NC-Pad8)") (class "Default")
      (node (ref "U15") (pin "8") (pinfunction "NC_8") (pintype "no_connect"))
    )
  )
)
